# robot_board.net
KiCad netlist of a schematic drawn in EAGLE
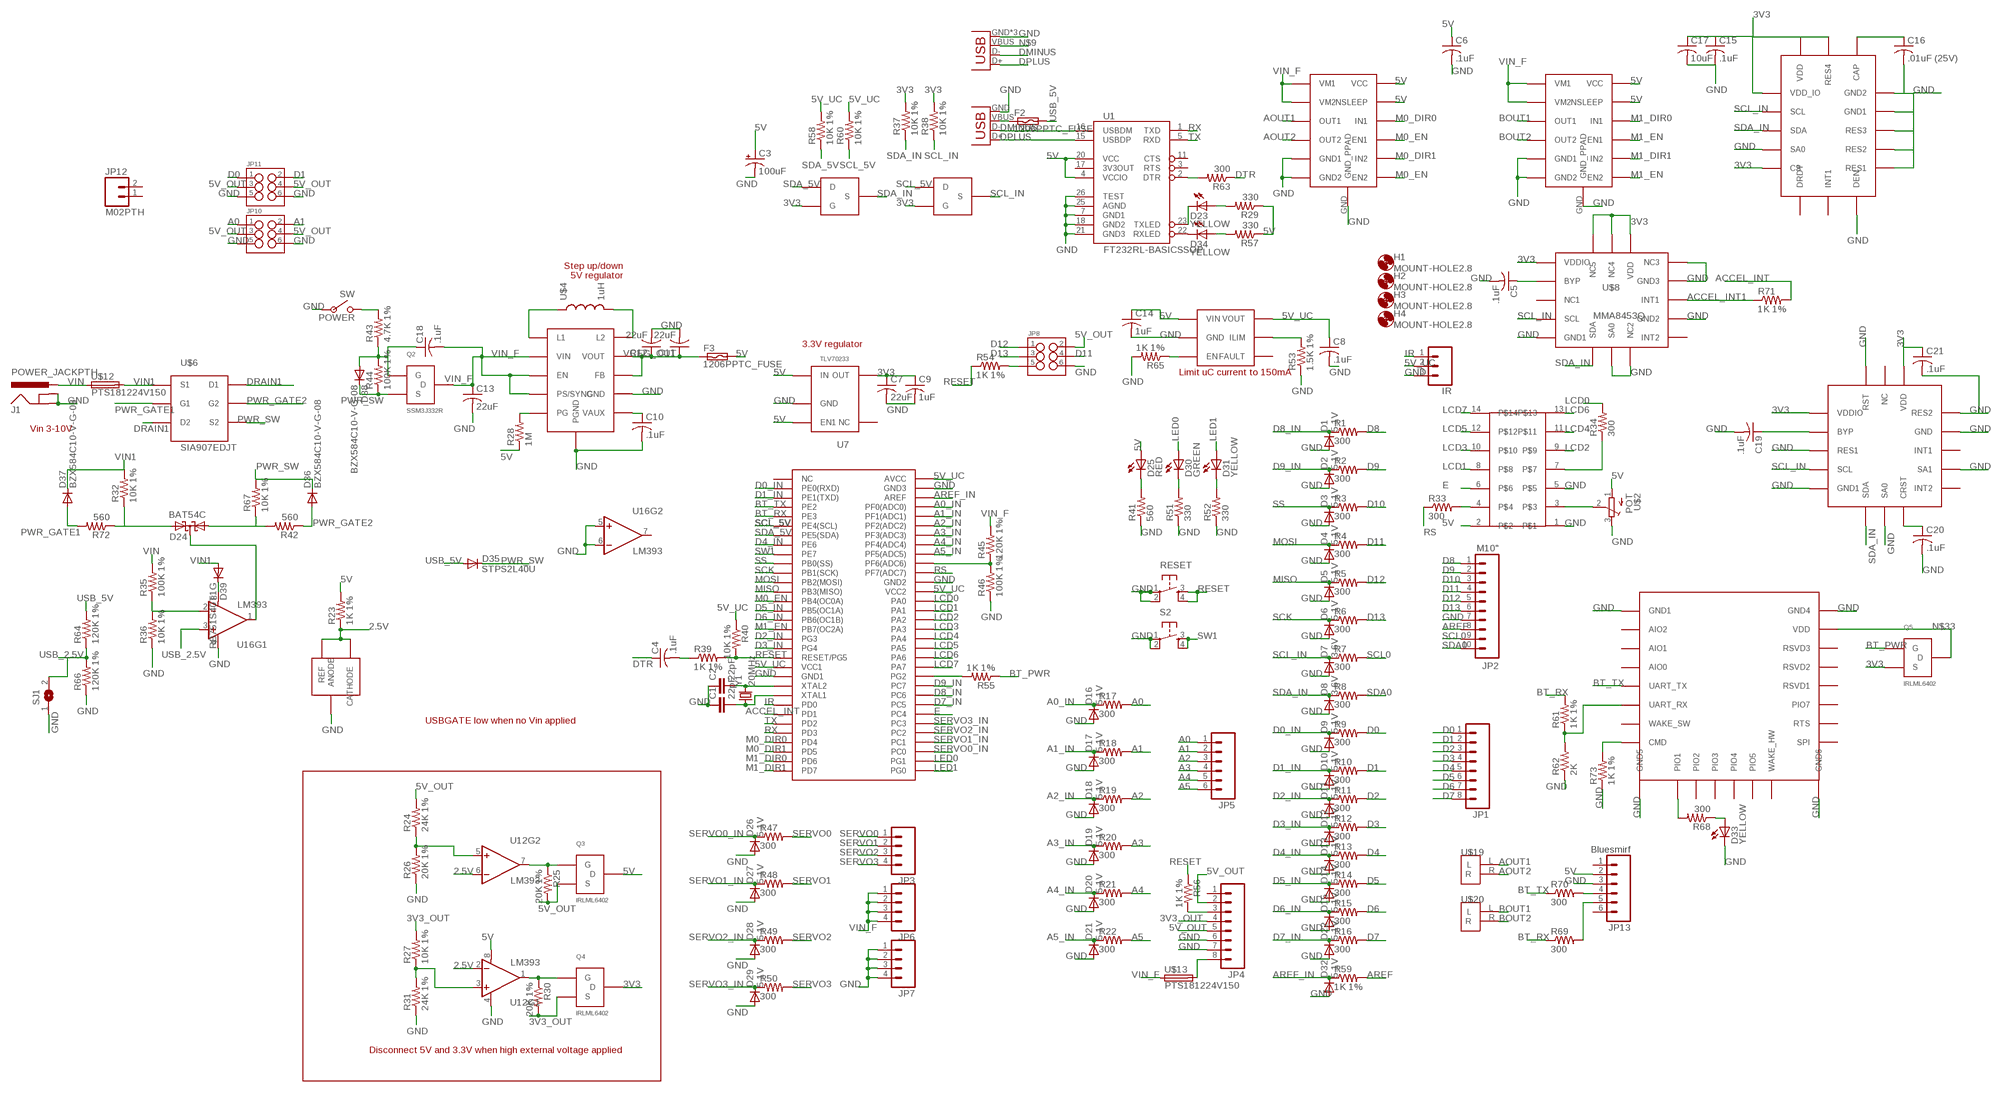
[diagram p0: schematic, sheet 1]

(export (version "E")
  (design (tool "Eeschema 10.0.6"))
  (components
    (comp (ref "C1")
      (value "22pF")
      (footprint "eagle-import:0805")
      (libsource (lib "eagle-import") (part "CAP0805"))
    )
    (comp (ref "C2")
      (value "22pF")
      (footprint "eagle-import:0805")
      (libsource (lib "eagle-import") (part "CAP0805"))
    )
    (comp (ref "C3")
      (value "100uF")
      (footprint "eagle-import:PANASONIC_D")
      (libsource (lib "eagle-import") (part "CAP_POLD"))
    )
    (comp (ref "C4")
      (value ".1uF")
      (footprint "eagle-import:C1206")
      (libsource (lib "eagle-import") (part "C-USC1206"))
    )
    (comp (ref "C5")
      (value ".1uF")
      (footprint "eagle-import:C1206")
      (libsource (lib "eagle-import") (part "C-USC1206"))
    )
    (comp (ref "C6")
      (value ".1uF")
      (footprint "eagle-import:C1206")
      (libsource (lib "eagle-import") (part "C-USC1206"))
    )
    (comp (ref "C7")
      (value "22uF")
      (footprint "eagle-import:C1206")
      (libsource (lib "eagle-import") (part "C-USC1206"))
    )
    (comp (ref "C8")
      (value ".1uF")
      (footprint "eagle-import:C1206")
      (libsource (lib "eagle-import") (part "C-USC1206"))
    )
    (comp (ref "C9")
      (value "1uF")
      (footprint "eagle-import:C1206")
      (libsource (lib "eagle-import") (part "C-USC1206"))
    )
    (comp (ref "C10")
      (value ".1uF")
      (footprint "eagle-import:C1206")
      (libsource (lib "eagle-import") (part "C-USC1206"))
    )
    (comp (ref "C11")
      (value "22uF")
      (footprint "eagle-import:C1206")
      (libsource (lib "eagle-import") (part "C-USC1206"))
    )
    (comp (ref "C12")
      (value "22uF")
      (footprint "eagle-import:C1206")
      (libsource (lib "eagle-import") (part "C-USC1206"))
    )
    (comp (ref "C13")
      (value "22uF")
      (footprint "eagle-import:C1206")
      (libsource (lib "eagle-import") (part "C-USC1206"))
    )
    (comp (ref "C14")
      (value "1uF")
      (footprint "eagle-import:C1206")
      (libsource (lib "eagle-import") (part "C-USC1206"))
    )
    (comp (ref "C15")
      (value ".1uF")
      (footprint "eagle-import:C1206")
      (libsource (lib "eagle-import") (part "C-USC1206"))
    )
    (comp (ref "C16")
      (value ".01uF (25V)")
      (footprint "eagle-import:C1206")
      (libsource (lib "eagle-import") (part "C-USC1206"))
    )
    (comp (ref "C17")
      (value "10uF")
      (footprint "eagle-import:C1206")
      (libsource (lib "eagle-import") (part "C-USC1206"))
    )
    (comp (ref "C18")
      (value ".1uF")
      (footprint "eagle-import:C1206")
      (libsource (lib "eagle-import") (part "C-USC1206"))
    )
    (comp (ref "C19")
      (value ".1uF")
      (footprint "eagle-import:C1206")
      (libsource (lib "eagle-import") (part "C-USC1206"))
    )
    (comp (ref "C20")
      (value ".1uF")
      (footprint "eagle-import:C1206")
      (libsource (lib "eagle-import") (part "C-USC1206"))
    )
    (comp (ref "C21")
      (value ".1uF")
      (footprint "eagle-import:C1206")
      (libsource (lib "eagle-import") (part "C-USC1206"))
    )
    (comp (ref "D1")
      (value "5.1V")
      (footprint "eagle-import:SOT23-3")
      (libsource (lib "eagle-import") (part "DIODESOT23"))
    )
    (comp (ref "D2")
      (value "5.1V")
      (footprint "eagle-import:SOT23-3")
      (libsource (lib "eagle-import") (part "DIODESOT23"))
    )
    (comp (ref "D3")
      (value "5.1V")
      (footprint "eagle-import:SOT23-3")
      (libsource (lib "eagle-import") (part "DIODESOT23"))
    )
    (comp (ref "D4")
      (value "5.1V")
      (footprint "eagle-import:SOT23-3")
      (libsource (lib "eagle-import") (part "DIODESOT23"))
    )
    (comp (ref "D5")
      (value "5.1V")
      (footprint "eagle-import:SOT23-3")
      (libsource (lib "eagle-import") (part "DIODESOT23"))
    )
    (comp (ref "D6")
      (value "5.1V")
      (footprint "eagle-import:SOT23-3")
      (libsource (lib "eagle-import") (part "DIODESOT23"))
    )
    (comp (ref "D7")
      (value "3.6V")
      (footprint "eagle-import:SOT23-3")
      (libsource (lib "eagle-import") (part "DIODESOT23"))
    )
    (comp (ref "D8")
      (value "3.6V")
      (footprint "eagle-import:SOT23-3")
      (libsource (lib "eagle-import") (part "DIODESOT23"))
    )
    (comp (ref "D9")
      (value "5.1V")
      (footprint "eagle-import:SOT23-3")
      (libsource (lib "eagle-import") (part "DIODESOT23"))
    )
    (comp (ref "D10")
      (value "5.1V")
      (footprint "eagle-import:SOT23-3")
      (libsource (lib "eagle-import") (part "DIODESOT23"))
    )
    (comp (ref "D11")
      (value "5.1V")
      (footprint "eagle-import:SOT23-3")
      (libsource (lib "eagle-import") (part "DIODESOT23"))
    )
    (comp (ref "D12")
      (value "5.1V")
      (footprint "eagle-import:SOT23-3")
      (libsource (lib "eagle-import") (part "DIODESOT23"))
    )
    (comp (ref "D13")
      (value "5.1V")
      (footprint "eagle-import:SOT23-3")
      (libsource (lib "eagle-import") (part "DIODESOT23"))
    )
    (comp (ref "D14")
      (value "5.1V")
      (footprint "eagle-import:SOT23-3")
      (libsource (lib "eagle-import") (part "DIODESOT23"))
    )
    (comp (ref "D15")
      (value "5.1V")
      (footprint "eagle-import:SOT23-3")
      (libsource (lib "eagle-import") (part "DIODESOT23"))
    )
    (comp (ref "D16")
      (value "5.1V")
      (footprint "eagle-import:SOT23-3")
      (libsource (lib "eagle-import") (part "DIODESOT23"))
    )
    (comp (ref "D17")
      (value "5.1V")
      (footprint "eagle-import:SOT23-3")
      (libsource (lib "eagle-import") (part "DIODESOT23"))
    )
    (comp (ref "D18")
      (value "5.1V")
      (footprint "eagle-import:SOT23-3")
      (libsource (lib "eagle-import") (part "DIODESOT23"))
    )
    (comp (ref "D19")
      (value "5.1V")
      (footprint "eagle-import:SOT23-3")
      (libsource (lib "eagle-import") (part "DIODESOT23"))
    )
    (comp (ref "D20")
      (value "5.1V")
      (footprint "eagle-import:SOT23-3")
      (libsource (lib "eagle-import") (part "DIODESOT23"))
    )
    (comp (ref "D21")
      (value "5.1V")
      (footprint "eagle-import:SOT23-3")
      (libsource (lib "eagle-import") (part "DIODESOT23"))
    )
    (comp (ref "D22")
      (value "5.1V")
      (footprint "eagle-import:SOT23-3")
      (libsource (lib "eagle-import") (part "DIODESOT23"))
    )
    (comp (ref "D23")
      (value "YELLOW")
      (footprint "eagle-import:LED-1206")
      (libsource (lib "eagle-import") (part "LED-GREENLILYPAD"))
    )
    (comp (ref "D24")
      (value "BAT54C")
      (footprint "eagle-import:SOT23")
      (libsource (lib "eagle-import") (part "BAT54C"))
    )
    (comp (ref "D25")
      (value "RED")
      (footprint "eagle-import:LED-1206")
      (libsource (lib "eagle-import") (part "LED-GREENLILYPAD"))
    )
    (comp (ref "D26")
      (value "5.1V")
      (footprint "eagle-import:SOT23-3")
      (libsource (lib "eagle-import") (part "DIODESOT23"))
    )
    (comp (ref "D27")
      (value "5.1V")
      (footprint "eagle-import:SOT23-3")
      (libsource (lib "eagle-import") (part "DIODESOT23"))
    )
    (comp (ref "D28")
      (value "5.1V")
      (footprint "eagle-import:SOT23-3")
      (libsource (lib "eagle-import") (part "DIODESOT23"))
    )
    (comp (ref "D29")
      (value "5.1V")
      (footprint "eagle-import:SOT23-3")
      (libsource (lib "eagle-import") (part "DIODESOT23"))
    )
    (comp (ref "D30")
      (value "GREEN")
      (footprint "eagle-import:LED-1206")
      (libsource (lib "eagle-import") (part "LED-GREENLILYPAD"))
    )
    (comp (ref "D31")
      (value "YELLOW")
      (footprint "eagle-import:LED-1206")
      (libsource (lib "eagle-import") (part "LED-GREENLILYPAD"))
    )
    (comp (ref "D32")
      (value "5.1V")
      (footprint "eagle-import:SOT23-3")
      (libsource (lib "eagle-import") (part "DIODESOT23"))
    )
    (comp (ref "D33")
      (value "YELLOW")
      (footprint "eagle-import:LED-1206")
      (libsource (lib "eagle-import") (part "LED-GREENLILYPAD"))
    )
    (comp (ref "D34")
      (value "YELLOW")
      (footprint "eagle-import:LED-1206")
      (libsource (lib "eagle-import") (part "LED-GREENLILYPAD"))
    )
    (comp (ref "D35")
      (value "STPS2L40U")
      (footprint "eagle-import:SMA-DIODE")
      (libsource (lib "eagle-import") (part "DIODESMA"))
    )
    (comp (ref "D36")
      (value "BZX584C10-V-G-08")
      (footprint "eagle-import:SOD523")
      (libsource (lib "eagle-import") (part "DIODESOD523"))
    )
    (comp (ref "D37")
      (value "BZX584C10-V-G-08")
      (footprint "eagle-import:SOD523")
      (libsource (lib "eagle-import") (part "DIODESOD523"))
    )
    (comp (ref "D38")
      (value "BZX584C10-V-G-08")
      (footprint "eagle-import:SOD523")
      (libsource (lib "eagle-import") (part "DIODESOD523"))
    )
    (comp (ref "D39")
      (value "RB751S40T1G")
      (footprint "eagle-import:SOD523")
      (libsource (lib "eagle-import") (part "DIODESOD523"))
    )
    (comp (ref "F2")
      (value "1206PPTC_FUSE")
      (footprint "eagle-import:R1206")
      (libsource (lib "eagle-import") (part "1206PPTC_FUSE"))
    )
    (comp (ref "F3")
      (value "1206PPTC_FUSE")
      (footprint "eagle-import:R1206")
      (libsource (lib "eagle-import") (part "1206PPTC_FUSE"))
    )
    (comp (ref "H1")
      (value "MOUNT-HOLE2.8")
      (footprint "eagle-import:2,8")
      (libsource (lib "eagle-import") (part "MOUNT-HOLE2.8"))
    )
    (comp (ref "H2")
      (value "MOUNT-HOLE2.8")
      (footprint "eagle-import:2,8")
      (libsource (lib "eagle-import") (part "MOUNT-HOLE2.8"))
    )
    (comp (ref "H3")
      (value "MOUNT-HOLE2.8")
      (footprint "eagle-import:2,8")
      (libsource (lib "eagle-import") (part "MOUNT-HOLE2.8"))
    )
    (comp (ref "H4")
      (value "MOUNT-HOLE2.8")
      (footprint "eagle-import:2,8")
      (libsource (lib "eagle-import") (part "MOUNT-HOLE2.8"))
    )
    (comp (ref "IR")
      (value "M03PTH")
      (footprint "eagle-import:1X03")
      (libsource (lib "eagle-import") (part "M03PTH"))
    )
    (comp (ref "J1")
      (value "POWER_JACKPTH")
      (footprint "eagle-import:POWER_JACK_PTH")
      (libsource (lib "eagle-import") (part "POWER_JACKPTH"))
    )
    (comp (ref "JP1")
      (value "M081X08")
      (footprint "eagle-import:1X08")
      (libsource (lib "eagle-import") (part "M081X08"))
    )
    (comp (ref "JP2")
      (value "M10\"")
      (footprint "eagle-import:1X10")
      (libsource (lib "eagle-import") (part "M10{dblquote}"))
    )
    (comp (ref "JP3")
      (value "M04PTH")
      (footprint "eagle-import:1X04")
      (libsource (lib "eagle-import") (part "M04PTH"))
    )
    (comp (ref "JP4")
      (value "M081X08")
      (footprint "eagle-import:1X08")
      (libsource (lib "eagle-import") (part "M081X08"))
    )
    (comp (ref "JP5")
      (value "M06SIP")
      (footprint "eagle-import:1X06")
      (libsource (lib "eagle-import") (part "M06SIP"))
    )
    (comp (ref "JP6")
      (value "M04PTH")
      (footprint "eagle-import:1X04")
      (libsource (lib "eagle-import") (part "M04PTH"))
    )
    (comp (ref "JP7")
      (value "M04PTH")
      (footprint "eagle-import:1X04")
      (libsource (lib "eagle-import") (part "M04PTH"))
    )
    (comp (ref "JP8")
      (value "M03X22X3_SILK_SM")
      (footprint "eagle-import:2X3")
      (libsource (lib "eagle-import") (part "M03X22X3_SILK_SM"))
    )
    (comp (ref "JP9")
      (value "USB-B")
      (footprint "eagle-import:USB-B-PTH")
      (libsource (lib "eagle-import") (part "USBPTH"))
    )
    (comp (ref "JP10")
      (value "M03X22X3_SILK_SM")
      (footprint "eagle-import:2X3")
      (libsource (lib "eagle-import") (part "M03X22X3_SILK_SM"))
    )
    (comp (ref "JP11")
      (value "M03X22X3_SILK_SM")
      (footprint "eagle-import:2X3")
      (libsource (lib "eagle-import") (part "M03X22X3_SILK_SM"))
    )
    (comp (ref "JP12")
      (value "M02PTH")
      (footprint "eagle-import:1X02")
      (libsource (lib "eagle-import") (part "M02PTH"))
    )
    (comp (ref "JP13")
      (value "Bluesmirf")
      (footprint "eagle-import:1X06")
      (libsource (lib "eagle-import") (part "M06SIP"))
    )
    (comp (ref "JP14")
      (value "USB-MICROB")
      (footprint "eagle-import:USB-MICROB")
      (libsource (lib "eagle-import") (part "USB-MICROB"))
    )
    (comp (ref "POWER")
      (value "SW")
      (footprint "eagle-import:SW")
      (libsource (lib "eagle-import") (part "SW"))
    )
    (comp (ref "Q2")
      (value "SSM3J332R")
      (footprint "eagle-import:SOT23")
      (libsource (lib "eagle-import") (part "DMP2035U"))
    )
    (comp (ref "Q3")
      (value "IRLML6402")
      (footprint "eagle-import:SOT23")
      (libsource (lib "eagle-import") (part "DMP2035U"))
    )
    (comp (ref "Q4")
      (value "IRLML6402")
      (footprint "eagle-import:SOT23")
      (libsource (lib "eagle-import") (part "DMP2035U"))
    )
    (comp (ref "Q5")
      (value "IRLML6402")
      (footprint "eagle-import:SOT23")
      (libsource (lib "eagle-import") (part "DMP2035U"))
    )
    (comp (ref "R1")
      (value "300")
      (footprint "eagle-import:R1206")
      (libsource (lib "eagle-import") (part "R-US_R1206"))
    )
    (comp (ref "R2")
      (value "300")
      (footprint "eagle-import:R1206")
      (libsource (lib "eagle-import") (part "R-US_R1206"))
    )
    (comp (ref "R3")
      (value "300")
      (footprint "eagle-import:R1206")
      (libsource (lib "eagle-import") (part "R-US_R1206"))
    )
    (comp (ref "R4")
      (value "300")
      (footprint "eagle-import:R1206")
      (libsource (lib "eagle-import") (part "R-US_R1206"))
    )
    (comp (ref "R5")
      (value "300")
      (footprint "eagle-import:R1206")
      (libsource (lib "eagle-import") (part "R-US_R1206"))
    )
    (comp (ref "R6")
      (value "300")
      (footprint "eagle-import:R1206")
      (libsource (lib "eagle-import") (part "R-US_R1206"))
    )
    (comp (ref "R7")
      (value "300")
      (footprint "eagle-import:R1206")
      (libsource (lib "eagle-import") (part "R-US_R1206"))
    )
    (comp (ref "R8")
      (value "300")
      (footprint "eagle-import:R1206")
      (libsource (lib "eagle-import") (part "R-US_R1206"))
    )
    (comp (ref "R9")
      (value "300")
      (footprint "eagle-import:R1206")
      (libsource (lib "eagle-import") (part "R-US_R1206"))
    )
    (comp (ref "R10")
      (value "300")
      (footprint "eagle-import:R1206")
      (libsource (lib "eagle-import") (part "R-US_R1206"))
    )
    (comp (ref "R11")
      (value "300")
      (footprint "eagle-import:R1206")
      (libsource (lib "eagle-import") (part "R-US_R1206"))
    )
    (comp (ref "R12")
      (value "300")
      (footprint "eagle-import:R1206")
      (libsource (lib "eagle-import") (part "R-US_R1206"))
    )
    (comp (ref "R13")
      (value "300")
      (footprint "eagle-import:R1206")
      (libsource (lib "eagle-import") (part "R-US_R1206"))
    )
    (comp (ref "R14")
      (value "300")
      (footprint "eagle-import:R1206")
      (libsource (lib "eagle-import") (part "R-US_R1206"))
    )
    (comp (ref "R15")
      (value "300")
      (footprint "eagle-import:R1206")
      (libsource (lib "eagle-import") (part "R-US_R1206"))
    )
    (comp (ref "R16")
      (value "300")
      (footprint "eagle-import:R1206")
      (libsource (lib "eagle-import") (part "R-US_R1206"))
    )
    (comp (ref "R17")
      (value "300")
      (footprint "eagle-import:R1206")
      (libsource (lib "eagle-import") (part "R-US_R1206"))
    )
    (comp (ref "R18")
      (value "300")
      (footprint "eagle-import:R1206")
      (libsource (lib "eagle-import") (part "R-US_R1206"))
    )
    (comp (ref "R19")
      (value "300")
      (footprint "eagle-import:R1206")
      (libsource (lib "eagle-import") (part "R-US_R1206"))
    )
    (comp (ref "R20")
      (value "300")
      (footprint "eagle-import:R1206")
      (libsource (lib "eagle-import") (part "R-US_R1206"))
    )
    (comp (ref "R21")
      (value "300")
      (footprint "eagle-import:R1206")
      (libsource (lib "eagle-import") (part "R-US_R1206"))
    )
    (comp (ref "R22")
      (value "300")
      (footprint "eagle-import:R1206")
      (libsource (lib "eagle-import") (part "R-US_R1206"))
    )
    (comp (ref "R23")
      (value "1K 1%")
      (footprint "eagle-import:R1206")
      (libsource (lib "eagle-import") (part "R-US_R1206"))
    )
    (comp (ref "R24")
      (value "24K 1%")
      (footprint "eagle-import:R1206")
      (libsource (lib "eagle-import") (part "R-US_R1206"))
    )
    (comp (ref "R25")
      (value "20K 1%")
      (footprint "eagle-import:R1206")
      (libsource (lib "eagle-import") (part "R-US_R1206"))
    )
    (comp (ref "R26")
      (value "20K 1%")
      (footprint "eagle-import:R1206")
      (libsource (lib "eagle-import") (part "R-US_R1206"))
    )
    (comp (ref "R27")
      (value "10K 1%")
      (footprint "eagle-import:R1206")
      (libsource (lib "eagle-import") (part "R-US_R1206"))
    )
    (comp (ref "R28")
      (value "1M")
      (footprint "eagle-import:R1206")
      (libsource (lib "eagle-import") (part "R-US_R1206"))
    )
    (comp (ref "R29")
      (value "330")
      (footprint "eagle-import:R1206")
      (libsource (lib "eagle-import") (part "R-US_R1206"))
    )
    (comp (ref "R30")
      (value "20K 1%")
      (footprint "eagle-import:R1206")
      (libsource (lib "eagle-import") (part "R-US_R1206"))
    )
    (comp (ref "R31")
      (value "24K 1%")
      (footprint "eagle-import:R1206")
      (libsource (lib "eagle-import") (part "R-US_R1206"))
    )
    (comp (ref "R32")
      (value "10K 1%")
      (footprint "eagle-import:R1206")
      (libsource (lib "eagle-import") (part "R-US_R1206"))
    )
    (comp (ref "R33")
      (value "300")
      (footprint "eagle-import:R1206")
      (libsource (lib "eagle-import") (part "R-US_R1206"))
    )
    (comp (ref "R34")
      (value "300")
      (footprint "eagle-import:R1206")
      (libsource (lib "eagle-import") (part "R-US_R1206"))
    )
    (comp (ref "R35")
      (value "100K 1%")
      (footprint "eagle-import:R1206")
      (libsource (lib "eagle-import") (part "R-US_R1206"))
    )
    (comp (ref "R36")
      (value "10K 1%")
      (footprint "eagle-import:R1206")
      (libsource (lib "eagle-import") (part "R-US_R1206"))
    )
    (comp (ref "R37")
      (value "10K 1%")
      (footprint "eagle-import:R1206")
      (libsource (lib "eagle-import") (part "R-US_R1206"))
    )
    (comp (ref "R38")
      (value "10K 1%")
      (footprint "eagle-import:R1206")
      (libsource (lib "eagle-import") (part "R-US_R1206"))
    )
    (comp (ref "R39")
      (value "1K 1%")
      (footprint "eagle-import:R1206")
      (libsource (lib "eagle-import") (part "R-US_R1206"))
    )
    (comp (ref "R40")
      (value "10K 1%")
      (footprint "eagle-import:R1206")
      (libsource (lib "eagle-import") (part "R-US_R1206"))
    )
    (comp (ref "R41")
      (value "560")
      (footprint "eagle-import:R1206")
      (libsource (lib "eagle-import") (part "R-US_R1206"))
    )
    (comp (ref "R42")
      (value "560")
      (footprint "eagle-import:R1206")
      (libsource (lib "eagle-import") (part "R-US_R1206"))
    )
    (comp (ref "R43")
      (value "4.7K 1%")
      (footprint "eagle-import:R1206")
      (libsource (lib "eagle-import") (part "R-US_R1206"))
    )
    (comp (ref "R44")
      (value "100K 1%")
      (footprint "eagle-import:R1206")
      (libsource (lib "eagle-import") (part "R-US_R1206"))
    )
    (comp (ref "R45")
      (value "120K 1%")
      (footprint "eagle-import:R1206")
      (libsource (lib "eagle-import") (part "R-US_R1206"))
    )
    (comp (ref "R46")
      (value "100K 1%")
      (footprint "eagle-import:R1206")
      (libsource (lib "eagle-import") (part "R-US_R1206"))
    )
    (comp (ref "R47")
      (value "300")
      (footprint "eagle-import:R1206")
      (libsource (lib "eagle-import") (part "R-US_R1206"))
    )
    (comp (ref "R48")
      (value "300")
      (footprint "eagle-import:R1206")
      (libsource (lib "eagle-import") (part "R-US_R1206"))
    )
    (comp (ref "R49")
      (value "300")
      (footprint "eagle-import:R1206")
      (libsource (lib "eagle-import") (part "R-US_R1206"))
    )
    (comp (ref "R50")
      (value "300")
      (footprint "eagle-import:R1206")
      (libsource (lib "eagle-import") (part "R-US_R1206"))
    )
    (comp (ref "R51")
      (value "330")
      (footprint "eagle-import:R1206")
      (libsource (lib "eagle-import") (part "R-US_R1206"))
    )
    (comp (ref "R52")
      (value "330")
      (footprint "eagle-import:R1206")
      (libsource (lib "eagle-import") (part "R-US_R1206"))
    )
    (comp (ref "R53")
      (value "1.5K 1%")
      (footprint "eagle-import:R1206")
      (libsource (lib "eagle-import") (part "R-US_R1206"))
    )
    (comp (ref "R54")
      (value "1K 1%")
      (footprint "eagle-import:R1206")
      (libsource (lib "eagle-import") (part "R-US_R1206"))
    )
    (comp (ref "R55")
      (value "1K 1%")
      (footprint "eagle-import:R1206")
      (libsource (lib "eagle-import") (part "R-US_R1206"))
    )
    (comp (ref "R56")
      (value "1K 1%")
      (footprint "eagle-import:R1206")
      (libsource (lib "eagle-import") (part "R-US_R1206"))
    )
    (comp (ref "R57")
      (value "330")
      (footprint "eagle-import:R1206")
      (libsource (lib "eagle-import") (part "R-US_R1206"))
    )
    (comp (ref "R58")
      (value "10K 1%")
      (footprint "eagle-import:R1206")
      (libsource (lib "eagle-import") (part "R-US_R1206"))
    )
    (comp (ref "R59")
      (value "1K 1%")
      (footprint "eagle-import:R1206")
      (libsource (lib "eagle-import") (part "R-US_R1206"))
    )
    (comp (ref "R60")
      (value "10K 1%")
      (footprint "eagle-import:R1206")
      (libsource (lib "eagle-import") (part "R-US_R1206"))
    )
    (comp (ref "R61")
      (value "1K 1%")
      (footprint "eagle-import:R1206")
      (libsource (lib "eagle-import") (part "R-US_R1206"))
    )
    (comp (ref "R62")
      (value "2K")
      (footprint "eagle-import:R1206")
      (libsource (lib "eagle-import") (part "R-US_R1206"))
    )
    (comp (ref "R63")
      (value "300")
      (footprint "eagle-import:R1206")
      (libsource (lib "eagle-import") (part "R-US_R1206"))
    )
    (comp (ref "R64")
      (value "120K 1%")
      (footprint "eagle-import:R1206")
      (libsource (lib "eagle-import") (part "R-US_R1206"))
    )
    (comp (ref "R65")
      (value "1K 1%")
      (footprint "eagle-import:R1206")
      (libsource (lib "eagle-import") (part "R-US_R1206"))
    )
    (comp (ref "R66")
      (value "120K 1%")
      (footprint "eagle-import:R1206")
      (libsource (lib "eagle-import") (part "R-US_R1206"))
    )
    (comp (ref "R67")
      (value "10K 1%")
      (footprint "eagle-import:R1206")
      (libsource (lib "eagle-import") (part "R-US_R1206"))
    )
    (comp (ref "R68")
      (value "300")
      (footprint "eagle-import:R1206")
      (libsource (lib "eagle-import") (part "R-US_R1206"))
    )
    (comp (ref "R69")
      (value "300")
      (footprint "eagle-import:R1206")
      (libsource (lib "eagle-import") (part "R-US_R1206"))
    )
    (comp (ref "R70")
      (value "300")
      (footprint "eagle-import:R1206")
      (libsource (lib "eagle-import") (part "R-US_R1206"))
    )
    (comp (ref "R71")
      (value "1K 1%")
      (footprint "eagle-import:R1206")
      (libsource (lib "eagle-import") (part "R-US_R1206"))
    )
    (comp (ref "R72")
      (value "560")
      (footprint "eagle-import:R1206")
      (libsource (lib "eagle-import") (part "R-US_R1206"))
    )
    (comp (ref "R73")
      (value "1K 1%")
      (footprint "eagle-import:R1206")
      (libsource (lib "eagle-import") (part "R-US_R1206"))
    )
    (comp (ref "RESET")
      (value "TAC_SWITCHPTH")
      (footprint "eagle-import:TACTILE-PTH")
      (libsource (lib "eagle-import") (part "TAC_SWITCHPTH"))
    )
    (comp (ref "S2")
      (value "TAC_SWITCHPTH")
      (footprint "eagle-import:TACTILE-PTH")
      (libsource (lib "eagle-import") (part "TAC_SWITCHPTH"))
    )
    (comp (ref "SJ1")
      (value "SJW")
      (footprint "eagle-import:SJW")
      (libsource (lib "eagle-import") (part "SJW"))
    )
    (comp (ref "U$1")
      (value "2X7HEADER")
      (footprint "eagle-import:2X7")
      (libsource (lib "eagle-import") (part "2X7HEADER"))
    )
    (comp (ref "U$2")
      (value "POT")
      (footprint "eagle-import:POT")
      (libsource (lib "eagle-import") (part "POT"))
    )
    (comp (ref "U$3")
      (value "TPS63061")
      (footprint "eagle-import:WSON-10")
      (libsource (lib "eagle-import") (part "TPS63061"))
    )
    (comp (ref "U$4")
      (value "1uH")
      (footprint "eagle-import:TAIYO4012")
      (libsource (lib "eagle-import") (part "TAIYO4012"))
    )
    (comp (ref "U$5")
      (value "AP431SAG-7")
      (footprint "eagle-import:SOT23")
      (libsource (lib "eagle-import") (part "AP431SAG-7"))
    )
    (comp (ref "U$6")
      (value "SIA907EDJT")
      (footprint "eagle-import:SC70T")
      (libsource (lib "eagle-import") (part "SIA907EDJT"))
    )
    (comp (ref "U$7")
      (value "RN4020")
      (footprint "eagle-import:RN4020_PKG")
      (libsource (lib "eagle-import") (part "RN4020"))
    )
    (comp (ref "U$8")
      (value "MMA8453Q")
      (footprint "eagle-import:QFN-COL")
      (libsource (lib "eagle-import") (part "MMA8453Q"))
    )
    (comp (ref "U$9")
      (value "BSS138")
      (footprint "eagle-import:SOT23")
      (libsource (lib "eagle-import") (part "BSS138"))
    )
    (comp (ref "U$10")
      (value "BSS138")
      (footprint "eagle-import:SOT23")
      (libsource (lib "eagle-import") (part "BSS138"))
    )
    (comp (ref "U$11")
      (value "L3GD20HTR")
      (footprint "eagle-import:LGA-16")
      (libsource (lib "eagle-import") (part "L3GD20HTR"))
    )
    (comp (ref "U$12")
      (value "PTS181224V150")
      (footprint "eagle-import:C1812")
      (libsource (lib "eagle-import") (part "PTS181224V150"))
    )
    (comp (ref "U$13")
      (value "PTS181224V150")
      (footprint "eagle-import:C1812")
      (libsource (lib "eagle-import") (part "PTS181224V150"))
    )
    (comp (ref "U$14")
      (value "FXOS8700CQ")
      (footprint "eagle-import:FSOS8700CQ_PKG")
      (libsource (lib "eagle-import") (part "FXOS8700CQ"))
    )
    (comp (ref "U$19")
      (value "2POS_TERMINAL")
      (footprint "eagle-import:2POS_TERMINAL")
      (libsource (lib "eagle-import") (part "2POS_TERMINAL"))
    )
    (comp (ref "U$20")
      (value "2POS_TERMINAL")
      (footprint "eagle-import:2POS_TERMINAL")
      (libsource (lib "eagle-import") (part "2POS_TERMINAL"))
    )
    (comp (ref "U1")
      (value "FT232RL-BASICSSOP")
      (footprint "eagle-import:SSOP28DB")
      (libsource (lib "eagle-import") (part "FT232RL-BASICSSOP"))
    )
    (comp (ref "U7")
      (value "TLV70233")
      (footprint "eagle-import:SOT-23-5")
      (libsource (lib "eagle-import") (part "TLV70233"))
    )
    (comp (ref "U8")
      (value "MIC2009A")
      (footprint "eagle-import:SOT23-M5")
      (libsource (lib "eagle-import") (part "MIC2009A"))
    )
    (comp (ref "U9")
      (value "DRV8839")
      (footprint "eagle-import:PWSON-N12")
      (libsource (lib "eagle-import") (part "DRV8839"))
    )
    (comp (ref "U10")
      (value "DRV8839")
      (footprint "eagle-import:PWSON-N12")
      (libsource (lib "eagle-import") (part "DRV8839"))
    )
    (comp (ref "U12")
      (value "LM393")
      (footprint "eagle-import:SO08")
      (libsource (lib "eagle-import") (part "LM393"))
    )
    (comp (ref "U16")
      (value "LM393")
      (footprint "eagle-import:SO08")
      (libsource (lib "eagle-import") (part "LM393"))
    )
    (comp (ref "U17")
      (value "ATMEGA325PA")
      (footprint "eagle-import:TQFP64")
      (libsource (lib "eagle-import") (part "ATMEGA325PA"))
    )
    (comp (ref "Y1")
      (value "20MHz")
      (footprint "eagle-import:CRYSTAL-SMD-10.5X4.8-2PIN")
      (libsource (lib "eagle-import") (part "CRYSTAL10.5X4.8"))
    )
  )
  (nets
    (net (code "1") (name "/2.5V") (class "Default")
      (node (ref "R23") (pin "1") (pinfunction "1_1") (pintype "passive"))
      (node (ref "U$5") (pin "1") (pinfunction "CATHODE_1") (pintype "bidirectional"))
      (node (ref "U$5") (pin "2") (pinfunction "REF_2") (pintype "bidirectional"))
      (node (ref "U12") (pin "2") (pinfunction "-IN_2") (pintype "input"))
      (node (ref "U12") (pin "6") (pinfunction "-IN_6") (pintype "input"))
    )
    (net (code "2") (name "/3V3") (class "Default")
      (node (ref "C15") (pin "1") (pinfunction "1_1") (pintype "passive"))
      (node (ref "C17") (pin "1") (pinfunction "1_1") (pintype "passive"))
      (node (ref "C21") (pin "1") (pinfunction "1_1") (pintype "passive"))
      (node (ref "C7") (pin "1") (pinfunction "1_1") (pintype "passive"))
      (node (ref "C9") (pin "1") (pinfunction "1_1") (pintype "passive"))
      (node (ref "Q4") (pin "3") (pinfunction "D_3") (pintype "bidirectional"))
      (node (ref "Q5") (pin "2") (pinfunction "S_2") (pintype "bidirectional"))
      (node (ref "R37") (pin "2") (pinfunction "2_2") (pintype "passive"))
      (node (ref "R38") (pin "2") (pinfunction "2_2") (pintype "passive"))
      (node (ref "U$10") (pin "1") (pinfunction "G_1") (pintype "bidirectional"))
      (node (ref "U$11") (pin "P$1") (pinfunction "VDD_IO_P$1") (pintype "bidirectional"))
      (node (ref "U$11") (pin "P$15") (pinfunction "RES4_P$15") (pintype "bidirectional"))
      (node (ref "U$11") (pin "P$16") (pinfunction "VDD_P$16") (pintype "bidirectional"))
      (node (ref "U$11") (pin "P$5") (pinfunction "CS_P$5") (pintype "bidirectional"))
      (node (ref "U$14") (pin "P$1") (pinfunction "VDDIO_P$1") (pintype "bidirectional"))
      (node (ref "U$14") (pin "P$14") (pinfunction "VDD_P$14") (pintype "bidirectional"))
      (node (ref "U$8") (pin "P$1") (pinfunction "VDDIO_P$1") (pintype "bidirectional"))
      (node (ref "U$8") (pin "P$14") (pinfunction "VDD_P$14") (pintype "bidirectional"))
      (node (ref "U$8") (pin "P$15") (pinfunction "NC4_P$15") (pintype "bidirectional"))
      (node (ref "U$8") (pin "P$16") (pinfunction "NC5_P$16") (pintype "bidirectional"))
      (node (ref "U$9") (pin "1") (pinfunction "G_1") (pintype "bidirectional"))
      (node (ref "U7") (pin "P$4") (pinfunction "OUT_P$4") (pintype "bidirectional"))
    )
    (net (code "3") (name "/3V3_OUT") (class "Default")
      (node (ref "JP4") (pin "4") (pinfunction "4_4") (pintype "passive"))
      (node (ref "Q4") (pin "2") (pinfunction "S_2") (pintype "bidirectional"))
      (node (ref "R27") (pin "2") (pinfunction "2_2") (pintype "passive"))
      (node (ref "R30") (pin "2") (pinfunction "2_2") (pintype "passive"))
    )
    (net (code "4") (name "/5V") (class "Default")
      (node (ref "C14") (pin "1") (pinfunction "1_1") (pintype "passive"))
      (node (ref "C3") (pin "+") (pinfunction "+_+") (pintype "passive"))
      (node (ref "C6") (pin "1") (pinfunction "1_1") (pintype "passive"))
      (node (ref "D25") (pin "A") (pinfunction "A_A") (pintype "passive"))
      (node (ref "F3") (pin "2") (pinfunction "2_2") (pintype "passive"))
      (node (ref "JP13") (pin "2") (pinfunction "2_2") (pintype "passive"))
      (node (ref "Q3") (pin "3") (pinfunction "D_3") (pintype "bidirectional"))
      (node (ref "R23") (pin "2") (pinfunction "2_2") (pintype "passive"))
      (node (ref "R28") (pin "1") (pinfunction "1_1") (pintype "passive"))
      (node (ref "R29") (pin "1") (pinfunction "1_1") (pintype "passive"))
      (node (ref "R57") (pin "1") (pinfunction "1_1") (pintype "passive"))
      (node (ref "U$1") (pin "2") (pinfunction "P$2_2") (pintype "bidirectional"))
      (node (ref "U$2") (pin "1") (pinfunction "A_1") (pintype "passive"))
      (node (ref "U1") (pin "20") (pinfunction "VCC_20") (pintype "power_in"))
      (node (ref "U1") (pin "4") (pinfunction "VCCIO_4") (pintype "power_in"))
      (node (ref "U10") (pin "P$7") (pinfunction "VCC_P$7") (pintype "bidirectional"))
      (node (ref "U10") (pin "P$8") (pinfunction "NSLEEP_P$8") (pintype "bidirectional"))
      (node (ref "U12") (pin "8") (pinfunction "V+_8") (pintype "power_in"))
      (node (ref "U7") (pin "P$1") (pinfunction "IN_P$1") (pintype "bidirectional"))
      (node (ref "U7") (pin "P$3") (pinfunction "EN1_P$3") (pintype "bidirectional"))
      (node (ref "U8") (pin "P$1") (pinfunction "VIN_P$1") (pintype "bidirectional"))
      (node (ref "U9") (pin "P$7") (pinfunction "VCC_P$7") (pintype "bidirectional"))
      (node (ref "U9") (pin "P$8") (pinfunction "NSLEEP_P$8") (pintype "bidirectional"))
    )
    (net (code "5") (name "/5V_OUT") (class "Default")
      (node (ref "JP10") (pin "3") (pinfunction "3_3") (pintype "bidirectional"))
      (node (ref "JP10") (pin "4") (pinfunction "4_4") (pintype "bidirectional"))
      (node (ref "JP11") (pin "3") (pinfunction "3_3") (pintype "bidirectional"))
      (node (ref "JP11") (pin "4") (pinfunction "4_4") (pintype "bidirectional"))
      (node (ref "JP4") (pin "2") (pinfunction "2_2") (pintype "passive"))
      (node (ref "JP4") (pin "5") (pinfunction "5_5") (pintype "passive"))
      (node (ref "JP8") (pin "2") (pinfunction "2_2") (pintype "bidirectional"))
      (node (ref "Q3") (pin "2") (pinfunction "S_2") (pintype "bidirectional"))
      (node (ref "R24") (pin "2") (pinfunction "2_2") (pintype "passive"))
      (node (ref "R25") (pin "2") (pinfunction "2_2") (pintype "passive"))
    )
    (net (code "6") (name "/5V_UC") (class "Default")
      (node (ref "C8") (pin "1") (pinfunction "1_1") (pintype "passive"))
      (node (ref "IR") (pin "2") (pinfunction "2_2") (pintype "passive"))
      (node (ref "R40") (pin "1") (pinfunction "1_1") (pintype "passive"))
      (node (ref "R58") (pin "2") (pinfunction "2_2") (pintype "passive"))
      (node (ref "R60") (pin "2") (pinfunction "2_2") (pintype "passive"))
      (node (ref "U17") (pin "21") (pinfunction "VCC1_21") (pintype "bidirectional"))
      (node (ref "U17") (pin "52") (pinfunction "VCC2_52") (pintype "bidirectional"))
      (node (ref "U17") (pin "64") (pinfunction "AVCC_64") (pintype "bidirectional"))
      (node (ref "U8") (pin "P$6") (pinfunction "VOUT_P$6") (pintype "bidirectional"))
    )
    (net (code "7") (name "/A0") (class "Default")
      (node (ref "JP10") (pin "1") (pinfunction "1_1") (pintype "bidirectional"))
      (node (ref "JP5") (pin "1") (pinfunction "1_1") (pintype "passive"))
      (node (ref "R17") (pin "2") (pinfunction "2_2") (pintype "passive"))
    )
    (net (code "8") (name "/A0_IN") (class "Default")
      (node (ref "D16") (pin "3") (pinfunction "C_3") (pintype "passive"))
      (node (ref "R17") (pin "1") (pinfunction "1_1") (pintype "passive"))
      (node (ref "U17") (pin "61") (pinfunction "PF0(ADC0)_61") (pintype "bidirectional"))
    )
    (net (code "9") (name "/A1") (class "Default")
      (node (ref "JP10") (pin "2") (pinfunction "2_2") (pintype "bidirectional"))
      (node (ref "JP5") (pin "2") (pinfunction "2_2") (pintype "passive"))
      (node (ref "R18") (pin "2") (pinfunction "2_2") (pintype "passive"))
    )
    (net (code "10") (name "/A1_IN") (class "Default")
      (node (ref "D17") (pin "3") (pinfunction "C_3") (pintype "passive"))
      (node (ref "R18") (pin "1") (pinfunction "1_1") (pintype "passive"))
      (node (ref "U17") (pin "60") (pinfunction "PF1(ADC1)_60") (pintype "bidirectional"))
    )
    (net (code "11") (name "/A2") (class "Default")
      (node (ref "JP5") (pin "3") (pinfunction "3_3") (pintype "passive"))
      (node (ref "R19") (pin "2") (pinfunction "2_2") (pintype "passive"))
    )
    (net (code "12") (name "/A2_IN") (class "Default")
      (node (ref "D18") (pin "3") (pinfunction "C_3") (pintype "passive"))
      (node (ref "R19") (pin "1") (pinfunction "1_1") (pintype "passive"))
      (node (ref "U17") (pin "59") (pinfunction "PF2(ADC2)_59") (pintype "bidirectional"))
    )
    (net (code "13") (name "/A3") (class "Default")
      (node (ref "JP5") (pin "4") (pinfunction "4_4") (pintype "passive"))
      (node (ref "R20") (pin "2") (pinfunction "2_2") (pintype "passive"))
    )
    (net (code "14") (name "/A3_IN") (class "Default")
      (node (ref "D19") (pin "3") (pinfunction "C_3") (pintype "passive"))
      (node (ref "R20") (pin "1") (pinfunction "1_1") (pintype "passive"))
      (node (ref "U17") (pin "58") (pinfunction "PF3(ADC3)_58") (pintype "bidirectional"))
    )
    (net (code "15") (name "/A4") (class "Default")
      (node (ref "JP5") (pin "5") (pinfunction "5_5") (pintype "passive"))
      (node (ref "R21") (pin "2") (pinfunction "2_2") (pintype "passive"))
    )
    (net (code "16") (name "/A4_IN") (class "Default")
      (node (ref "D20") (pin "3") (pinfunction "C_3") (pintype "passive"))
      (node (ref "R21") (pin "1") (pinfunction "1_1") (pintype "passive"))
      (node (ref "U17") (pin "57") (pinfunction "PF4(ADC4)_57") (pintype "bidirectional"))
    )
    (net (code "17") (name "/A5") (class "Default")
      (node (ref "JP5") (pin "6") (pinfunction "6_6") (pintype "passive"))
      (node (ref "R22") (pin "2") (pinfunction "2_2") (pintype "passive"))
    )
    (net (code "18") (name "/A5_IN") (class "Default")
      (node (ref "D21") (pin "3") (pinfunction "C_3") (pintype "passive"))
      (node (ref "R22") (pin "1") (pinfunction "1_1") (pintype "passive"))
      (node (ref "U17") (pin "56") (pinfunction "PF5(ADC5)_56") (pintype "bidirectional"))
    )
    (net (code "19") (name "/ACCEL_INT") (class "Default")
      (node (ref "R71") (pin "2") (pinfunction "2_2") (pintype "passive"))
      (node (ref "U17") (pin "26") (pinfunction "PD1_26") (pintype "bidirectional"))
    )
    (net (code "20") (name "/ACCEL_INT1") (class "Default")
      (node (ref "R71") (pin "1") (pinfunction "1_1") (pintype "passive"))
      (node (ref "U$8") (pin "P$11") (pinfunction "INT1_P$11") (pintype "bidirectional"))
    )
    (net (code "21") (name "/AOUT1") (class "Default")
      (node (ref "U$19") (pin "L") (pinfunction "L_L") (pintype "bidirectional"))
      (node (ref "U9") (pin "P$3") (pinfunction "OUT1_P$3") (pintype "bidirectional"))
    )
    (net (code "22") (name "/AOUT2") (class "Default")
      (node (ref "U$19") (pin "R") (pinfunction "R_R") (pintype "bidirectional"))
      (node (ref "U9") (pin "P$4") (pinfunction "OUT2_P$4") (pintype "bidirectional"))
    )
    (net (code "23") (name "/AREF") (class "Default")
      (node (ref "JP2") (pin "8") (pinfunction "8_8") (pintype "passive"))
      (node (ref "R59") (pin "2") (pinfunction "2_2") (pintype "passive"))
    )
    (net (code "24") (name "/AREF_IN") (class "Default")
      (node (ref "D32") (pin "3") (pinfunction "C_3") (pintype "passive"))
      (node (ref "R59") (pin "1") (pinfunction "1_1") (pintype "passive"))
      (node (ref "U17") (pin "62") (pinfunction "AREF_62") (pintype "bidirectional"))
    )
    (net (code "25") (name "/BOUT1") (class "Default")
      (node (ref "U$20") (pin "L") (pinfunction "L_L") (pintype "bidirectional"))
      (node (ref "U10") (pin "P$3") (pinfunction "OUT1_P$3") (pintype "bidirectional"))
    )
    (net (code "26") (name "/BOUT2") (class "Default")
      (node (ref "U$20") (pin "R") (pinfunction "R_R") (pintype "bidirectional"))
      (node (ref "U10") (pin "P$4") (pinfunction "OUT2_P$4") (pintype "bidirectional"))
    )
    (net (code "27") (name "/BT_PWR") (class "Default")
      (node (ref "Q5") (pin "1") (pinfunction "G_1") (pintype "bidirectional"))
      (node (ref "R55") (pin "1") (pinfunction "1_1") (pintype "passive"))
    )
    (net (code "28") (name "/BT_RX") (class "Default")
      (node (ref "R61") (pin "2") (pinfunction "2_2") (pintype "passive"))
      (node (ref "R69") (pin "1") (pinfunction "1_1") (pintype "passive"))
      (node (ref "U17") (pin "5") (pinfunction "PE3_5") (pintype "bidirectional"))
    )
    (net (code "29") (name "/BT_TX") (class "Default")
      (node (ref "R70") (pin "1") (pinfunction "1_1") (pintype "passive"))
      (node (ref "U$7") (pin "P$5") (pinfunction "UART_TX_P$5") (pintype "bidirectional"))
      (node (ref "U17") (pin "4") (pinfunction "PE2_4") (pintype "bidirectional"))
    )
    (net (code "30") (name "/D0") (class "Default")
      (node (ref "JP1") (pin "1") (pinfunction "1_1") (pintype "passive"))
      (node (ref "JP11") (pin "1") (pinfunction "1_1") (pintype "bidirectional"))
      (node (ref "R9") (pin "2") (pinfunction "2_2") (pintype "passive"))
    )
    (net (code "31") (name "/D0_IN") (class "Default")
      (node (ref "D9") (pin "3") (pinfunction "C_3") (pintype "passive"))
      (node (ref "R9") (pin "1") (pinfunction "1_1") (pintype "passive"))
      (node (ref "U17") (pin "2") (pinfunction "PE0(RXD)_2") (pintype "bidirectional"))
    )
    (net (code "32") (name "/D1") (class "Default")
      (node (ref "JP1") (pin "2") (pinfunction "2_2") (pintype "passive"))
      (node (ref "JP11") (pin "2") (pinfunction "2_2") (pintype "bidirectional"))
      (node (ref "R10") (pin "2") (pinfunction "2_2") (pintype "passive"))
    )
    (net (code "33") (name "/D1_IN") (class "Default")
      (node (ref "D10") (pin "3") (pinfunction "C_3") (pintype "passive"))
      (node (ref "R10") (pin "1") (pinfunction "1_1") (pintype "passive"))
      (node (ref "U17") (pin "3") (pinfunction "PE1(TXD)_3") (pintype "bidirectional"))
    )
    (net (code "34") (name "/D2") (class "Default")
      (node (ref "JP1") (pin "3") (pinfunction "3_3") (pintype "passive"))
      (node (ref "R11") (pin "2") (pinfunction "2_2") (pintype "passive"))
    )
    (net (code "35") (name "/D2_IN") (class "Default")
      (node (ref "D11") (pin "3") (pinfunction "C_3") (pintype "passive"))
      (node (ref "R11") (pin "1") (pinfunction "1_1") (pintype "passive"))
      (node (ref "U17") (pin "18") (pinfunction "PG3_18") (pintype "bidirectional"))
    )
    (net (code "36") (name "/D3") (class "Default")
      (node (ref "JP1") (pin "4") (pinfunction "4_4") (pintype "passive"))
      (node (ref "R12") (pin "2") (pinfunction "2_2") (pintype "passive"))
    )
    (net (code "37") (name "/D3_IN") (class "Default")
      (node (ref "D12") (pin "3") (pinfunction "C_3") (pintype "passive"))
      (node (ref "R12") (pin "1") (pinfunction "1_1") (pintype "passive"))
      (node (ref "U17") (pin "19") (pinfunction "PG4_19") (pintype "bidirectional"))
    )
    (net (code "38") (name "/D4") (class "Default")
      (node (ref "JP1") (pin "5") (pinfunction "5_5") (pintype "passive"))
      (node (ref "R13") (pin "2") (pinfunction "2_2") (pintype "passive"))
    )
    (net (code "39") (name "/D4_IN") (class "Default")
      (node (ref "D13") (pin "3") (pinfunction "C_3") (pintype "passive"))
      (node (ref "R13") (pin "1") (pinfunction "1_1") (pintype "passive"))
      (node (ref "U17") (pin "8") (pinfunction "PE6_8") (pintype "bidirectional"))
    )
    (net (code "40") (name "/D5") (class "Default")
      (node (ref "JP1") (pin "6") (pinfunction "6_6") (pintype "passive"))
      (node (ref "R14") (pin "2") (pinfunction "2_2") (pintype "passive"))
    )
    (net (code "41") (name "/D5_IN") (class "Default")
      (node (ref "D14") (pin "3") (pinfunction "C_3") (pintype "passive"))
      (node (ref "R14") (pin "1") (pinfunction "1_1") (pintype "passive"))
      (node (ref "U17") (pin "15") (pinfunction "PB5(OC1A)_15") (pintype "bidirectional"))
    )
    (net (code "42") (name "/D6") (class "Default")
      (node (ref "JP1") (pin "7") (pinfunction "7_7") (pintype "passive"))
      (node (ref "R15") (pin "2") (pinfunction "2_2") (pintype "passive"))
    )
    (net (code "43") (name "/D6_IN") (class "Default")
      (node (ref "D15") (pin "3") (pinfunction "C_3") (pintype "passive"))
      (node (ref "R15") (pin "1") (pinfunction "1_1") (pintype "passive"))
      (node (ref "U17") (pin "16") (pinfunction "PB6(OC1B)_16") (pintype "bidirectional"))
    )
    (net (code "44") (name "/D7") (class "Default")
      (node (ref "JP1") (pin "8") (pinfunction "8_8") (pintype "passive"))
      (node (ref "R16") (pin "2") (pinfunction "2_2") (pintype "passive"))
    )
    (net (code "45") (name "/D7_IN") (class "Default")
      (node (ref "D22") (pin "3") (pinfunction "C_3") (pintype "passive"))
      (node (ref "R16") (pin "1") (pinfunction "1_1") (pintype "passive"))
      (node (ref "U17") (pin "40") (pinfunction "PC5_40") (pintype "bidirectional"))
    )
    (net (code "46") (name "/D8") (class "Default")
      (node (ref "JP2") (pin "1") (pinfunction "1_1") (pintype "passive"))
      (node (ref "R1") (pin "2") (pinfunction "2_2") (pintype "passive"))
    )
    (net (code "47") (name "/D8_IN") (class "Default")
      (node (ref "D1") (pin "3") (pinfunction "C_3") (pintype "passive"))
      (node (ref "R1") (pin "1") (pinfunction "1_1") (pintype "passive"))
      (node (ref "U17") (pin "41") (pinfunction "PC6_41") (pintype "bidirectional"))
    )
    (net (code "48") (name "/D9") (class "Default")
      (node (ref "JP2") (pin "2") (pinfunction "2_2") (pintype "passive"))
      (node (ref "R2") (pin "2") (pinfunction "2_2") (pintype "passive"))
    )
    (net (code "49") (name "/D9_IN") (class "Default")
      (node (ref "D2") (pin "3") (pinfunction "C_3") (pintype "passive"))
      (node (ref "R2") (pin "1") (pinfunction "1_1") (pintype "passive"))
      (node (ref "U17") (pin "42") (pinfunction "PC7_42") (pintype "bidirectional"))
    )
    (net (code "50") (name "/D10") (class "Default")
      (node (ref "JP2") (pin "3") (pinfunction "3_3") (pintype "passive"))
      (node (ref "R3") (pin "2") (pinfunction "2_2") (pintype "passive"))
    )
    (net (code "51") (name "/D11") (class "Default")
      (node (ref "JP2") (pin "4") (pinfunction "4_4") (pintype "passive"))
      (node (ref "JP8") (pin "4") (pinfunction "4_4") (pintype "bidirectional"))
      (node (ref "R4") (pin "2") (pinfunction "2_2") (pintype "passive"))
    )
    (net (code "52") (name "/D12") (class "Default")
      (node (ref "JP2") (pin "5") (pinfunction "5_5") (pintype "passive"))
      (node (ref "JP8") (pin "1") (pinfunction "1_1") (pintype "bidirectional"))
      (node (ref "R5") (pin "2") (pinfunction "2_2") (pintype "passive"))
    )
    (net (code "53") (name "/D13") (class "Default")
      (node (ref "JP2") (pin "6") (pinfunction "6_6") (pintype "passive"))
      (node (ref "JP8") (pin "3") (pinfunction "3_3") (pintype "bidirectional"))
      (node (ref "R6") (pin "2") (pinfunction "2_2") (pintype "passive"))
    )
    (net (code "54") (name "/DMINUS") (class "Default")
      (node (ref "JP14") (pin "D-") (pinfunction "D-_D-") (pintype "bidirectional"))
      (node (ref "JP9") (pin "D-") (pinfunction "D-_D-") (pintype "bidirectional"))
      (node (ref "U1") (pin "16") (pinfunction "USBDM_16") (pintype "bidirectional"))
    )
    (net (code "55") (name "/DPLUS") (class "Default")
      (node (ref "JP14") (pin "D+") (pinfunction "D+_D+") (pintype "bidirectional"))
      (node (ref "JP9") (pin "D+") (pinfunction "D+_D+") (pintype "bidirectional"))
      (node (ref "U1") (pin "15") (pinfunction "USBDP_15") (pintype "bidirectional"))
    )
    (net (code "56") (name "/DRAIN1") (class "Default")
      (node (ref "U$6") (pin "D1@1") (pinfunction "D1_D1@1") (pintype "bidirectional"))
      (node (ref "U$6") (pin "D1@2") (pinfunction "D1_D1@2") (pintype "bidirectional"))
      (node (ref "U$6") (pin "D2@1") (pinfunction "D2_D2@1") (pintype "bidirectional"))
      (node (ref "U$6") (pin "D2@2") (pinfunction "D2_D2@2") (pintype "bidirectional"))
    )
    (net (code "57") (name "/DTR") (class "Default")
      (node (ref "C4") (pin "1") (pinfunction "1_1") (pintype "passive"))
      (node (ref "R63") (pin "1") (pinfunction "1_1") (pintype "passive"))
    )
    (net (code "58") (name "/E") (class "Default")
      (node (ref "U$1") (pin "6") (pinfunction "P$6_6") (pintype "bidirectional"))
      (node (ref "U17") (pin "39") (pinfunction "PC4_39") (pintype "bidirectional"))
    )
    (net (code "59") (name "/GND") (class "Default")
      (node (ref "C1") (pin "1") (pinfunction "1_1") (pintype "passive"))
      (node (ref "C10") (pin "2") (pinfunction "2_2") (pintype "passive"))
      (node (ref "C11") (pin "2") (pinfunction "2_2") (pintype "passive"))
      (node (ref "C12") (pin "2") (pinfunction "2_2") (pintype "passive"))
      (node (ref "C13") (pin "2") (pinfunction "2_2") (pintype "passive"))
      (node (ref "C14") (pin "2") (pinfunction "2_2") (pintype "passive"))
      (node (ref "C15") (pin "2") (pinfunction "2_2") (pintype "passive"))
      (node (ref "C16") (pin "2") (pinfunction "2_2") (pintype "passive"))
      (node (ref "C17") (pin "2") (pinfunction "2_2") (pintype "passive"))
      (node (ref "C19") (pin "2") (pinfunction "2_2") (pintype "passive"))
      (node (ref "C2") (pin "1") (pinfunction "1_1") (pintype "passive"))
      (node (ref "C20") (pin "2") (pinfunction "2_2") (pintype "passive"))
      (node (ref "C21") (pin "2") (pinfunction "2_2") (pintype "passive"))
      (node (ref "C3") (pin "-") (pinfunction "-_-") (pintype "passive"))
      (node (ref "C5") (pin "2") (pinfunction "2_2") (pintype "passive"))
      (node (ref "C6") (pin "2") (pinfunction "2_2") (pintype "passive"))
      (node (ref "C7") (pin "2") (pinfunction "2_2") (pintype "passive"))
      (node (ref "C8") (pin "2") (pinfunction "2_2") (pintype "passive"))
      (node (ref "C9") (pin "2") (pinfunction "2_2") (pintype "passive"))
      (node (ref "D1") (pin "1") (pinfunction "A_1") (pintype "passive"))
      (node (ref "D10") (pin "1") (pinfunction "A_1") (pintype "passive"))
      (node (ref "D11") (pin "1") (pinfunction "A_1") (pintype "passive"))
      (node (ref "D12") (pin "1") (pinfunction "A_1") (pintype "passive"))
      (node (ref "D13") (pin "1") (pinfunction "A_1") (pintype "passive"))
      (node (ref "D14") (pin "1") (pinfunction "A_1") (pintype "passive"))
      (node (ref "D15") (pin "1") (pinfunction "A_1") (pintype "passive"))
      (node (ref "D16") (pin "1") (pinfunction "A_1") (pintype "passive"))
      (node (ref "D17") (pin "1") (pinfunction "A_1") (pintype "passive"))
      (node (ref "D18") (pin "1") (pinfunction "A_1") (pintype "passive"))
      (node (ref "D19") (pin "1") (pinfunction "A_1") (pintype "passive"))
      (node (ref "D2") (pin "1") (pinfunction "A_1") (pintype "passive"))
      (node (ref "D20") (pin "1") (pinfunction "A_1") (pintype "passive"))
      (node (ref "D21") (pin "1") (pinfunction "A_1") (pintype "passive"))
      (node (ref "D22") (pin "1") (pinfunction "A_1") (pintype "passive"))
      (node (ref "D26") (pin "1") (pinfunction "A_1") (pintype "passive"))
      (node (ref "D27") (pin "1") (pinfunction "A_1") (pintype "passive"))
      (node (ref "D28") (pin "1") (pinfunction "A_1") (pintype "passive"))
      (node (ref "D29") (pin "1") (pinfunction "A_1") (pintype "passive"))
      (node (ref "D3") (pin "1") (pinfunction "A_1") (pintype "passive"))
      (node (ref "D32") (pin "1") (pinfunction "A_1") (pintype "passive"))
      (node (ref "D33") (pin "C") (pinfunction "C_C") (pintype "passive"))
      (node (ref "D4") (pin "1") (pinfunction "A_1") (pintype "passive"))
      (node (ref "D5") (pin "1") (pinfunction "A_1") (pintype "passive"))
      (node (ref "D6") (pin "1") (pinfunction "A_1") (pintype "passive"))
      (node (ref "D7") (pin "1") (pinfunction "A_1") (pintype "passive"))
      (node (ref "D8") (pin "1") (pinfunction "A_1") (pintype "passive"))
      (node (ref "D9") (pin "1") (pinfunction "A_1") (pintype "passive"))
      (node (ref "IR") (pin "3") (pinfunction "3_3") (pintype "passive"))
      (node (ref "J1") (pin "GND") (pinfunction "GND_GND") (pintype "bidirectional"))
      (node (ref "J1") (pin "GNDBREAK") (pinfunction "GNDBREAK_GNDBREAK") (pintype "bidirectional"))
      (node (ref "JP10") (pin "5") (pinfunction "5_5") (pintype "bidirectional"))
      (node (ref "JP10") (pin "6") (pinfunction "6_6") (pintype "bidirectional"))
      (node (ref "JP11") (pin "5") (pinfunction "5_5") (pintype "bidirectional"))
      (node (ref "JP11") (pin "6") (pinfunction "6_6") (pintype "bidirectional"))
      (node (ref "JP13") (pin "3") (pinfunction "3_3") (pintype "passive"))
      (node (ref "JP14") (pin "GND") (pinfunction "GND_GND") (pintype "bidirectional"))
      (node (ref "JP14") (pin "MT1") (pinfunction "GND_MT1") (pintype "bidirectional"))
      (node (ref "JP14") (pin "MT2") (pinfunction "GND_MT2") (pintype "bidirectional"))
      (node (ref "JP2") (pin "7") (pinfunction "7_7") (pintype "passive"))
      (node (ref "JP4") (pin "6") (pinfunction "6_6") (pintype "passive"))
      (node (ref "JP4") (pin "7") (pinfunction "7_7") (pintype "passive"))
      (node (ref "JP7") (pin "1") (pinfunction "1_1") (pintype "passive"))
      (node (ref "JP7") (pin "2") (pinfunction "2_2") (pintype "passive"))
      (node (ref "JP7") (pin "3") (pinfunction "3_3") (pintype "passive"))
      (node (ref "JP7") (pin "4") (pinfunction "4_4") (pintype "passive"))
      (node (ref "JP8") (pin "6") (pinfunction "6_6") (pintype "bidirectional"))
      (node (ref "JP9") (pin "GND") (pinfunction "GND_GND") (pintype "bidirectional"))
      (node (ref "POWER") (pin "P$2") (pinfunction "P$2_P$2") (pintype "bidirectional"))
      (node (ref "R26") (pin "1") (pinfunction "1_1") (pintype "passive"))
      (node (ref "R31") (pin "1") (pinfunction "1_1") (pintype "passive"))
      (node (ref "R36") (pin "1") (pinfunction "1_1") (pintype "passive"))
      (node (ref "R41") (pin "1") (pinfunction "1_1") (pintype "passive"))
      (node (ref "R46") (pin "1") (pinfunction "1_1") (pintype "passive"))
      (node (ref "R51") (pin "1") (pinfunction "1_1") (pintype "passive"))
      (node (ref "R52") (pin "1") (pinfunction "1_1") (pintype "passive"))
      (node (ref "R53") (pin "1") (pinfunction "1_1") (pintype "passive"))
      (node (ref "R62") (pin "1") (pinfunction "1_1") (pintype "passive"))
      (node (ref "R65") (pin "2") (pinfunction "2_2") (pintype "passive"))
      (node (ref "R66") (pin "1") (pinfunction "1_1") (pintype "passive"))
      (node (ref "R73") (pin "1") (pinfunction "1_1") (pintype "passive"))
      (node (ref "RESET") (pin "1") (pinfunction "1_1") (pintype "passive"))
      (node (ref "RESET") (pin "2") (pinfunction "2_2") (pintype "passive"))
      (node (ref "S2") (pin "1") (pinfunction "1_1") (pintype "passive"))
      (node (ref "S2") (pin "2") (pinfunction "2_2") (pintype "passive"))
      (node (ref "SJ1") (pin "1") (pinfunction "1_1") (pintype "passive"))
      (node (ref "U$1") (pin "1") (pinfunction "P$1_1") (pintype "bidirectional"))
      (node (ref "U$1") (pin "5") (pinfunction "P$5_5") (pintype "bidirectional"))
      (node (ref "U$11") (pin "P$10") (pinfunction "RES2_P$10") (pintype "bidirectional"))
      (node (ref "U$11") (pin "P$11") (pinfunction "RES3_P$11") (pintype "bidirectional"))
      (node (ref "U$11") (pin "P$12") (pinfunction "GND1_P$12") (pintype "bidirectional"))
      (node (ref "U$11") (pin "P$13") (pinfunction "GND2_P$13") (pintype "bidirectional"))
      (node (ref "U$11") (pin "P$4") (pinfunction "SA0_P$4") (pintype "bidirectional"))
      (node (ref "U$11") (pin "P$8") (pinfunction "DEN_P$8") (pintype "bidirectional"))
      (node (ref "U$11") (pin "P$9") (pinfunction "RES1_P$9") (pintype "bidirectional"))
      (node (ref "U$14") (pin "P$10") (pinfunction "SA1_P$10") (pintype "bidirectional"))
      (node (ref "U$14") (pin "P$12") (pinfunction "GND_P$12") (pintype "bidirectional"))
      (node (ref "U$14") (pin "P$13") (pinfunction "RES2_P$13") (pintype "bidirectional"))
      (node (ref "U$14") (pin "P$16") (pinfunction "RST_P$16") (pintype "bidirectional"))
      (node (ref "U$14") (pin "P$3") (pinfunction "RES1_P$3") (pintype "bidirectional"))
      (node (ref "U$14") (pin "P$5") (pinfunction "GND1_P$5") (pintype "bidirectional"))
      (node (ref "U$14") (pin "P$7") (pinfunction "SA0_P$7") (pintype "bidirectional"))
      (node (ref "U$2") (pin "3") (pinfunction "E_3") (pintype "passive"))
      (node (ref "U$3") (pin "GND@N1") (pinfunction "PGND_GND@N1") (pintype "bidirectional"))
      (node (ref "U$3") (pin "GND@N2") (pinfunction "PGND_GND@N2") (pintype "bidirectional"))
      (node (ref "U$3") (pin "GND@N3") (pinfunction "PGND_GND@N3") (pintype "bidirectional"))
      (node (ref "U$3") (pin "GND@N4") (pinfunction "PGND_GND@N4") (pintype "bidirectional"))
      (node (ref "U$3") (pin "GND@N5") (pinfunction "PGND_GND@N5") (pintype "bidirectional"))
      (node (ref "U$3") (pin "GND@N6") (pinfunction "PGND_GND@N6") (pintype "bidirectional"))
      (node (ref "U$3") (pin "GND@N7") (pinfunction "PGND_GND@N7") (pintype "bidirectional"))
      (node (ref "U$3") (pin "GND@N8") (pinfunction "PGND_GND@N8") (pintype "bidirectional"))
      (node (ref "U$3") (pin "P$11") (pinfunction "PGND_P$11") (pintype "bidirectional"))
      (node (ref "U$3") (pin "P$7") (pinfunction "GND_P$7") (pintype "bidirectional"))
      (node (ref "U$5") (pin "3") (pinfunction "ANODE_3") (pintype "bidirectional"))
      (node (ref "U$7") (pin "P$1") (pinfunction "GND1_P$1") (pintype "bidirectional"))
      (node (ref "U$7") (pin "P$22") (pinfunction "GND4_P$22") (pintype "bidirectional"))
      (node (ref "U$7") (pin "P$23") (pinfunction "GND5_P$23") (pintype "bidirectional"))
      (node (ref "U$7") (pin "P$24") (pinfunction "GND6_P$24") (pintype "bidirectional"))
      (node (ref "U$8") (pin "P$10") (pinfunction "GND2_P$10") (pintype "bidirectional"))
      (node (ref "U$8") (pin "P$12") (pinfunction "GND3_P$12") (pintype "bidirectional"))
      (node (ref "U$8") (pin "P$13") (pinfunction "NC3_P$13") (pintype "bidirectional"))
      (node (ref "U$8") (pin "P$5") (pinfunction "GND1_P$5") (pintype "bidirectional"))
      (node (ref "U$8") (pin "P$7") (pinfunction "SA0_P$7") (pintype "bidirectional"))
      (node (ref "U$8") (pin "P$8") (pinfunction "NC2_P$8") (pintype "bidirectional"))
      (node (ref "U1") (pin "18") (pinfunction "GND2_18") (pintype "power_in"))
      (node (ref "U1") (pin "21") (pinfunction "GND3_21") (pintype "power_in"))
      (node (ref "U1") (pin "25") (pinfunction "AGND_25") (pintype "power_in"))
      (node (ref "U1") (pin "26") (pinfunction "TEST_26") (pintype "input"))
      (node (ref "U1") (pin "7") (pinfunction "GND1_7") (pintype "power_in"))
      (node (ref "U10") (pin "GND") (pinfunction "GND_PPAD_GND") (pintype "bidirectional"))
      (node (ref "U10") (pin "P$5") (pinfunction "GND1_P$5") (pintype "bidirectional"))
      (node (ref "U10") (pin "P$6") (pinfunction "GND2_P$6") (pintype "bidirectional"))
      (node (ref "U12") (pin "4") (pinfunction "V-_4") (pintype "power_in"))
      (node (ref "U16") (pin "4") (pinfunction "V-_4") (pintype "power_in"))
      (node (ref "U16") (pin "5") (pinfunction "+IN_5") (pintype "input"))
      (node (ref "U16") (pin "6") (pinfunction "-IN_6") (pintype "input"))
      (node (ref "U17") (pin "22") (pinfunction "GND1_22") (pintype "bidirectional"))
      (node (ref "U17") (pin "53") (pinfunction "GND2_53") (pintype "bidirectional"))
      (node (ref "U17") (pin "63") (pinfunction "GND3_63") (pintype "bidirectional"))
      (node (ref "U7") (pin "P$2") (pinfunction "GND_P$2") (pintype "bidirectional"))
      (node (ref "U8") (pin "P$2") (pinfunction "GND_P$2") (pintype "bidirectional"))
      (node (ref "U9") (pin "GND") (pinfunction "GND_PPAD_GND") (pintype "bidirectional"))
      (node (ref "U9") (pin "P$5") (pinfunction "GND1_P$5") (pintype "bidirectional"))
      (node (ref "U9") (pin "P$6") (pinfunction "GND2_P$6") (pintype "bidirectional"))
    )
    (net (code "60") (name "/IR") (class "Default")
      (node (ref "IR") (pin "1") (pinfunction "1_1") (pintype "passive"))
      (node (ref "U17") (pin "25") (pinfunction "PD0_25") (pintype "bidirectional"))
    )
    (net (code "61") (name "/LCD0") (class "Default")
      (node (ref "R34") (pin "2") (pinfunction "2_2") (pintype "passive"))
      (node (ref "U17") (pin "51") (pinfunction "PA0_51") (pintype "bidirectional"))
    )
    (net (code "62") (name "/LCD1") (class "Default")
      (node (ref "U$1") (pin "8") (pinfunction "P$8_8") (pintype "bidirectional"))
      (node (ref "U17") (pin "50") (pinfunction "PA1_50") (pintype "bidirectional"))
    )
    (net (code "63") (name "/LCD2") (class "Default")
      (node (ref "U$1") (pin "9") (pinfunction "P$9_9") (pintype "bidirectional"))
      (node (ref "U17") (pin "49") (pinfunction "PA2_49") (pintype "bidirectional"))
    )
    (net (code "64") (name "/LCD3") (class "Default")
      (node (ref "U$1") (pin "10") (pinfunction "P$10_10") (pintype "bidirectional"))
      (node (ref "U17") (pin "48") (pinfunction "PA3_48") (pintype "bidirectional"))
    )
    (net (code "65") (name "/LCD4") (class "Default")
      (node (ref "U$1") (pin "11") (pinfunction "P$11_11") (pintype "bidirectional"))
      (node (ref "U17") (pin "47") (pinfunction "PA4_47") (pintype "bidirectional"))
    )
    (net (code "66") (name "/LCD5") (class "Default")
      (node (ref "U$1") (pin "12") (pinfunction "P$12_12") (pintype "bidirectional"))
      (node (ref "U17") (pin "46") (pinfunction "PA5_46") (pintype "bidirectional"))
    )
    (net (code "67") (name "/LCD6") (class "Default")
      (node (ref "U$1") (pin "13") (pinfunction "P$13_13") (pintype "bidirectional"))
      (node (ref "U17") (pin "45") (pinfunction "PA6_45") (pintype "bidirectional"))
    )
    (net (code "68") (name "/LCD7") (class "Default")
      (node (ref "U$1") (pin "14") (pinfunction "P$14_14") (pintype "bidirectional"))
      (node (ref "U17") (pin "44") (pinfunction "PA7_44") (pintype "bidirectional"))
    )
    (net (code "69") (name "/LED0") (class "Default")
      (node (ref "D30") (pin "A") (pinfunction "A_A") (pintype "passive"))
      (node (ref "U17") (pin "34") (pinfunction "PG1_34") (pintype "bidirectional"))
    )
    (net (code "70") (name "/LED1") (class "Default")
      (node (ref "D31") (pin "A") (pinfunction "A_A") (pintype "passive"))
      (node (ref "U17") (pin "33") (pinfunction "PG0_33") (pintype "bidirectional"))
    )
    (net (code "71") (name "/M0_DIR0") (class "Default")
      (node (ref "U17") (pin "29") (pinfunction "PD4_29") (pintype "bidirectional"))
      (node (ref "U9") (pin "P$9") (pinfunction "IN1_P$9") (pintype "bidirectional"))
    )
    (net (code "72") (name "/M0_DIR1") (class "Default")
      (node (ref "U17") (pin "30") (pinfunction "PD5_30") (pintype "bidirectional"))
      (node (ref "U9") (pin "P$11") (pinfunction "IN2_P$11") (pintype "bidirectional"))
    )
    (net (code "73") (name "/M0_EN") (class "Default")
      (node (ref "U17") (pin "14") (pinfunction "PB4(OC0A)_14") (pintype "bidirectional"))
      (node (ref "U9") (pin "P$10") (pinfunction "EN1_P$10") (pintype "bidirectional"))
      (node (ref "U9") (pin "P$12") (pinfunction "EN2_P$12") (pintype "bidirectional"))
    )
    (net (code "74") (name "/M1_DIR0") (class "Default")
      (node (ref "U10") (pin "P$9") (pinfunction "IN1_P$9") (pintype "bidirectional"))
      (node (ref "U17") (pin "31") (pinfunction "PD6_31") (pintype "bidirectional"))
    )
    (net (code "75") (name "/M1_DIR1") (class "Default")
      (node (ref "U10") (pin "P$11") (pinfunction "IN2_P$11") (pintype "bidirectional"))
      (node (ref "U17") (pin "32") (pinfunction "PD7_32") (pintype "bidirectional"))
    )
    (net (code "76") (name "/M1_EN") (class "Default")
      (node (ref "U10") (pin "P$10") (pinfunction "EN1_P$10") (pintype "bidirectional"))
      (node (ref "U10") (pin "P$12") (pinfunction "EN2_P$12") (pintype "bidirectional"))
      (node (ref "U17") (pin "17") (pinfunction "PB7(OC2A)_17") (pintype "bidirectional"))
    )
    (net (code "77") (name "/MISO") (class "Default")
      (node (ref "D5") (pin "3") (pinfunction "C_3") (pintype "passive"))
      (node (ref "R5") (pin "1") (pinfunction "1_1") (pintype "passive"))
      (node (ref "U17") (pin "13") (pinfunction "PB3(MISO)_13") (pintype "bidirectional"))
    )
    (net (code "78") (name "/MOSI") (class "Default")
      (node (ref "D4") (pin "3") (pinfunction "C_3") (pintype "passive"))
      (node (ref "R4") (pin "1") (pinfunction "1_1") (pintype "passive"))
      (node (ref "U17") (pin "12") (pinfunction "PB2(MOSI)_12") (pintype "bidirectional"))
    )
    (net (code "79") (name "/N$9") (class "Default")
      (node (ref "F2") (pin "1") (pinfunction "1_1") (pintype "passive"))
      (node (ref "JP14") (pin "VBUS") (pinfunction "VBUS_VBUS") (pintype "bidirectional"))
      (node (ref "JP9") (pin "VBUS") (pinfunction "VBUS_VBUS") (pintype "bidirectional"))
    )
    (net (code "80") (name "/N$33") (class "Default")
      (node (ref "Q5") (pin "3") (pinfunction "D_3") (pintype "bidirectional"))
      (node (ref "U$7") (pin "P$21") (pinfunction "VDD_P$21") (pintype "bidirectional"))
    )
    (net (code "81") (name "/PWR_GATE1") (class "Default")
      (node (ref "D37") (pin "A") (pinfunction "A_A") (pintype "passive"))
      (node (ref "R72") (pin "2") (pinfunction "2_2") (pintype "passive"))
      (node (ref "U$6") (pin "G1") (pinfunction "G1_G1") (pintype "bidirectional"))
    )
    (net (code "82") (name "/PWR_GATE2") (class "Default")
      (node (ref "D36") (pin "A") (pinfunction "A_A") (pintype "passive"))
      (node (ref "R42") (pin "1") (pinfunction "1_1") (pintype "passive"))
      (node (ref "U$6") (pin "G2") (pinfunction "G2_G2") (pintype "bidirectional"))
    )
    (net (code "83") (name "/PWR_SW") (class "Default")
      (node (ref "D35") (pin "C") (pinfunction "C_C") (pintype "passive"))
      (node (ref "D36") (pin "C") (pinfunction "C_C") (pintype "passive"))
      (node (ref "D38") (pin "C") (pinfunction "C_C") (pintype "passive"))
      (node (ref "Q2") (pin "2") (pinfunction "S_2") (pintype "bidirectional"))
      (node (ref "R44") (pin "1") (pinfunction "1_1") (pintype "passive"))
      (node (ref "R67") (pin "2") (pinfunction "2_2") (pintype "passive"))
      (node (ref "U$6") (pin "S2") (pinfunction "S2_S2") (pintype "bidirectional"))
    )
    (net (code "84") (name "/RESET") (class "Default")
      (node (ref "R39") (pin "2") (pinfunction "2_2") (pintype "passive"))
      (node (ref "R40") (pin "2") (pinfunction "2_2") (pintype "passive"))
      (node (ref "R54") (pin "1") (pinfunction "1_1") (pintype "passive"))
      (node (ref "R56") (pin "1") (pinfunction "1_1") (pintype "passive"))
      (node (ref "RESET") (pin "3") (pinfunction "3_3") (pintype "passive"))
      (node (ref "RESET") (pin "4") (pinfunction "4_4") (pintype "passive"))
      (node (ref "U17") (pin "20") (pinfunction "RESET/PG5_20") (pintype "bidirectional"))
    )
    (net (code "85") (name "/RS") (class "Default")
      (node (ref "R33") (pin "1") (pinfunction "1_1") (pintype "passive"))
      (node (ref "U17") (pin "54") (pinfunction "PF7(ADC7)_54") (pintype "bidirectional"))
    )
    (net (code "86") (name "/RX") (class "Default")
      (node (ref "U1") (pin "1") (pinfunction "TXD_1") (pintype "output"))
      (node (ref "U17") (pin "28") (pinfunction "PD3_28") (pintype "bidirectional"))
    )
    (net (code "87") (name "/SCK") (class "Default")
      (node (ref "D6") (pin "3") (pinfunction "C_3") (pintype "passive"))
      (node (ref "R6") (pin "1") (pinfunction "1_1") (pintype "passive"))
      (node (ref "U17") (pin "11") (pinfunction "PB1(SCK)_11") (pintype "bidirectional"))
    )
    (net (code "88") (name "/SCL0") (class "Default")
      (node (ref "JP2") (pin "9") (pinfunction "9_9") (pintype "passive"))
      (node (ref "R7") (pin "2") (pinfunction "2_2") (pintype "passive"))
    )
    (net (code "89") (name "/SCL_5V") (class "Default")
      (node (ref "R60") (pin "1") (pinfunction "1_1") (pintype "passive"))
      (node (ref "U$10") (pin "3") (pinfunction "D_3") (pintype "bidirectional"))
      (node (ref "U17") (pin "6") (pinfunction "PE4(SCL)_6") (pintype "bidirectional"))
    )
    (net (code "90") (name "/SCL_IN") (class "Default")
      (node (ref "D7") (pin "3") (pinfunction "C_3") (pintype "passive"))
      (node (ref "R38") (pin "1") (pinfunction "1_1") (pintype "passive"))
      (node (ref "R7") (pin "1") (pinfunction "1_1") (pintype "passive"))
      (node (ref "U$10") (pin "2") (pinfunction "S_2") (pintype "bidirectional"))
      (node (ref "U$11") (pin "P$2") (pinfunction "SCL_P$2") (pintype "bidirectional"))
      (node (ref "U$14") (pin "P$4") (pinfunction "SCL_P$4") (pintype "bidirectional"))
      (node (ref "U$8") (pin "P$4") (pinfunction "SCL_P$4") (pintype "bidirectional"))
    )
    (net (code "91") (name "/SDA0") (class "Default")
      (node (ref "JP2") (pin "10") (pinfunction "10_10") (pintype "passive"))
      (node (ref "R8") (pin "2") (pinfunction "2_2") (pintype "passive"))
    )
    (net (code "92") (name "/SDA_5V") (class "Default")
      (node (ref "R58") (pin "1") (pinfunction "1_1") (pintype "passive"))
      (node (ref "U$9") (pin "3") (pinfunction "D_3") (pintype "bidirectional"))
      (node (ref "U17") (pin "7") (pinfunction "PE5(SDA)_7") (pintype "bidirectional"))
    )
    (net (code "93") (name "/SDA_IN") (class "Default")
      (node (ref "D8") (pin "3") (pinfunction "C_3") (pintype "passive"))
      (node (ref "R37") (pin "1") (pinfunction "1_1") (pintype "passive"))
      (node (ref "R8") (pin "1") (pinfunction "1_1") (pintype "passive"))
      (node (ref "U$11") (pin "P$3") (pinfunction "SDA_P$3") (pintype "bidirectional"))
      (node (ref "U$14") (pin "P$6") (pinfunction "SDA_P$6") (pintype "bidirectional"))
      (node (ref "U$8") (pin "P$6") (pinfunction "SDA_P$6") (pintype "bidirectional"))
      (node (ref "U$9") (pin "2") (pinfunction "S_2") (pintype "bidirectional"))
    )
    (net (code "94") (name "/SERVO0") (class "Default")
      (node (ref "JP3") (pin "1") (pinfunction "1_1") (pintype "passive"))
      (node (ref "R47") (pin "2") (pinfunction "2_2") (pintype "passive"))
    )
    (net (code "95") (name "/SERVO0_IN") (class "Default")
      (node (ref "D26") (pin "3") (pinfunction "C_3") (pintype "passive"))
      (node (ref "R47") (pin "1") (pinfunction "1_1") (pintype "passive"))
      (node (ref "U17") (pin "35") (pinfunction "PC0_35") (pintype "bidirectional"))
    )
    (net (code "96") (name "/SERVO1") (class "Default")
      (node (ref "JP3") (pin "2") (pinfunction "2_2") (pintype "passive"))
      (node (ref "R48") (pin "2") (pinfunction "2_2") (pintype "passive"))
    )
    (net (code "97") (name "/SERVO1_IN") (class "Default")
      (node (ref "D27") (pin "3") (pinfunction "C_3") (pintype "passive"))
      (node (ref "R48") (pin "1") (pinfunction "1_1") (pintype "passive"))
      (node (ref "U17") (pin "36") (pinfunction "PC1_36") (pintype "bidirectional"))
    )
    (net (code "98") (name "/SERVO2") (class "Default")
      (node (ref "JP3") (pin "3") (pinfunction "3_3") (pintype "passive"))
      (node (ref "R49") (pin "2") (pinfunction "2_2") (pintype "passive"))
    )
    (net (code "99") (name "/SERVO2_IN") (class "Default")
      (node (ref "D28") (pin "3") (pinfunction "C_3") (pintype "passive"))
      (node (ref "R49") (pin "1") (pinfunction "1_1") (pintype "passive"))
      (node (ref "U17") (pin "37") (pinfunction "PC2_37") (pintype "bidirectional"))
    )
    (net (code "100") (name "/SERVO3") (class "Default")
      (node (ref "JP3") (pin "4") (pinfunction "4_4") (pintype "passive"))
      (node (ref "R50") (pin "2") (pinfunction "2_2") (pintype "passive"))
    )
    (net (code "101") (name "/SERVO3_IN") (class "Default")
      (node (ref "D29") (pin "3") (pinfunction "C_3") (pintype "passive"))
      (node (ref "R50") (pin "1") (pinfunction "1_1") (pintype "passive"))
      (node (ref "U17") (pin "38") (pinfunction "PC3_38") (pintype "bidirectional"))
    )
    (net (code "102") (name "/SS") (class "Default")
      (node (ref "D3") (pin "3") (pinfunction "C_3") (pintype "passive"))
      (node (ref "R3") (pin "1") (pinfunction "1_1") (pintype "passive"))
      (node (ref "U17") (pin "10") (pinfunction "PB0(SS)_10") (pintype "bidirectional"))
    )
    (net (code "103") (name "/SW1") (class "Default")
      (node (ref "S2") (pin "3") (pinfunction "3_3") (pintype "passive"))
      (node (ref "S2") (pin "4") (pinfunction "4_4") (pintype "passive"))
      (node (ref "U17") (pin "9") (pinfunction "PE7_9") (pintype "bidirectional"))
    )
    (net (code "104") (name "/TX") (class "Default")
      (node (ref "U1") (pin "5") (pinfunction "RXD_5") (pintype "input"))
      (node (ref "U17") (pin "27") (pinfunction "PD2_27") (pintype "bidirectional"))
    )
    (net (code "105") (name "/USB_2.5V") (class "Default")
      (node (ref "R64") (pin "1") (pinfunction "1_1") (pintype "passive"))
      (node (ref "R66") (pin "2") (pinfunction "2_2") (pintype "passive"))
      (node (ref "SJ1") (pin "2") (pinfunction "2_2") (pintype "passive"))
      (node (ref "U16") (pin "3") (pinfunction "+IN_3") (pintype "input"))
    )
    (net (code "106") (name "/USB_5V") (class "Default")
      (node (ref "D35") (pin "A") (pinfunction "A_A") (pintype "passive"))
      (node (ref "F2") (pin "2") (pinfunction "2_2") (pintype "passive"))
      (node (ref "R64") (pin "2") (pinfunction "2_2") (pintype "passive"))
    )
    (net (code "107") (name "/VIN") (class "Default")
      (node (ref "J1") (pin "PWR") (pinfunction "PWR_PWR") (pintype "bidirectional"))
      (node (ref "R35") (pin "2") (pinfunction "2_2") (pintype "passive"))
      (node (ref "U$12") (pin "1") (pinfunction "1_1") (pintype "passive"))
    )
    (net (code "108") (name "/VIN1") (class "Default")
      (node (ref "D37") (pin "C") (pinfunction "C_C") (pintype "passive"))
      (node (ref "D39") (pin "A") (pinfunction "A_A") (pintype "passive"))
      (node (ref "R32") (pin "2") (pinfunction "2_2") (pintype "passive"))
      (node (ref "U$12") (pin "2") (pinfunction "2_2") (pintype "passive"))
      (node (ref "U$6") (pin "S1") (pinfunction "S1_S1") (pintype "bidirectional"))
    )
    (net (code "109") (name "/VIN_F") (class "Default")
      (node (ref "C13") (pin "1") (pinfunction "1_1") (pintype "passive"))
      (node (ref "C18") (pin "2") (pinfunction "2_2") (pintype "passive"))
      (node (ref "JP6") (pin "1") (pinfunction "1_1") (pintype "passive"))
      (node (ref "JP6") (pin "2") (pinfunction "2_2") (pintype "passive"))
      (node (ref "JP6") (pin "3") (pinfunction "3_3") (pintype "passive"))
      (node (ref "JP6") (pin "4") (pinfunction "4_4") (pintype "passive"))
      (node (ref "Q2") (pin "3") (pinfunction "D_3") (pintype "bidirectional"))
      (node (ref "R45") (pin "2") (pinfunction "2_2") (pintype "passive"))
      (node (ref "U$13") (pin "1") (pinfunction "1_1") (pintype "passive"))
      (node (ref "U$3") (pin "P$2") (pinfunction "VIN_P$2") (pintype "bidirectional"))
      (node (ref "U$3") (pin "P$3") (pinfunction "EN_P$3") (pintype "bidirectional"))
      (node (ref "U$3") (pin "P$4") (pinfunction "PS/SYNC_P$4") (pintype "bidirectional"))
      (node (ref "U10") (pin "P$1") (pinfunction "VM1_P$1") (pintype "bidirectional"))
      (node (ref "U10") (pin "P$2") (pinfunction "VM2_P$2") (pintype "bidirectional"))
      (node (ref "U9") (pin "P$1") (pinfunction "VM1_P$1") (pintype "bidirectional"))
      (node (ref "U9") (pin "P$2") (pinfunction "VM2_P$2") (pintype "bidirectional"))
    )
    (net (code "110") (name "/VREG_OUT") (class "Default")
      (node (ref "C11") (pin "1") (pinfunction "1_1") (pintype "passive"))
      (node (ref "C12") (pin "1") (pinfunction "1_1") (pintype "passive"))
      (node (ref "F3") (pin "1") (pinfunction "1_1") (pintype "passive"))
      (node (ref "U$3") (pin "P$8") (pinfunction "FB_P$8") (pintype "bidirectional"))
      (node (ref "U$3") (pin "P$9") (pinfunction "VOUT_P$9") (pintype "bidirectional"))
    )
    (net (code "111") (name "Net-(C4-Pad2)") (class "Default")
      (node (ref "C4") (pin "2") (pinfunction "2_2") (pintype "passive"))
      (node (ref "R39") (pin "1") (pinfunction "1_1") (pintype "passive"))
    )
    (net (code "112") (name "Net-(D23-PadA)") (class "Default")
      (node (ref "D23") (pin "A") (pinfunction "A_A") (pintype "passive"))
      (node (ref "R29") (pin "2") (pinfunction "2_2") (pintype "passive"))
    )
    (net (code "113") (name "Net-(D24-A1)") (class "Default")
      (node (ref "D24") (pin "1") (pinfunction "A1_1") (pintype "passive"))
      (node (ref "R42") (pin "2") (pinfunction "2_2") (pintype "passive"))
      (node (ref "R67") (pin "1") (pinfunction "1_1") (pintype "passive"))
    )
    (net (code "114") (name "Net-(D24-A2)") (class "Default")
      (node (ref "D24") (pin "2") (pinfunction "A2_2") (pintype "passive"))
      (node (ref "R32") (pin "1") (pinfunction "1_1") (pintype "passive"))
      (node (ref "R72") (pin "1") (pinfunction "1_1") (pintype "passive"))
    )
    (net (code "115") (name "Net-(D24-CC)") (class "Default")
      (node (ref "D24") (pin "3") (pinfunction "CC_3") (pintype "passive"))
      (node (ref "U16") (pin "1") (pinfunction "OUT_1") (pintype "output"))
    )
    (net (code "116") (name "Net-(D25-PadC)") (class "Default")
      (node (ref "D25") (pin "C") (pinfunction "C_C") (pintype "passive"))
      (node (ref "R41") (pin "2") (pinfunction "2_2") (pintype "passive"))
    )
    (net (code "117") (name "Net-(D30-PadC)") (class "Default")
      (node (ref "D30") (pin "C") (pinfunction "C_C") (pintype "passive"))
      (node (ref "R51") (pin "2") (pinfunction "2_2") (pintype "passive"))
    )
    (net (code "118") (name "Net-(D31-PadC)") (class "Default")
      (node (ref "D31") (pin "C") (pinfunction "C_C") (pintype "passive"))
      (node (ref "R52") (pin "2") (pinfunction "2_2") (pintype "passive"))
    )
    (net (code "119") (name "Net-(D33-PadA)") (class "Default")
      (node (ref "D33") (pin "A") (pinfunction "A_A") (pintype "passive"))
      (node (ref "R68") (pin "1") (pinfunction "1_1") (pintype "passive"))
    )
    (net (code "120") (name "Net-(D34-PadA)") (class "Default")
      (node (ref "D34") (pin "A") (pinfunction "A_A") (pintype "passive"))
      (node (ref "R57") (pin "2") (pinfunction "2_2") (pintype "passive"))
    )
    (net (code "121") (name "Net-(JP4-Pad3)") (class "Default")
      (node (ref "JP4") (pin "3") (pinfunction "3_3") (pintype "passive"))
      (node (ref "R56") (pin "2") (pinfunction "2_2") (pintype "passive"))
    )
    (net (code "122") (name "Net-(JP4-Pad8)") (class "Default")
      (node (ref "JP4") (pin "8") (pinfunction "8_8") (pintype "passive"))
      (node (ref "U$13") (pin "2") (pinfunction "2_2") (pintype "passive"))
    )
    (net (code "123") (name "Net-(JP8-Pad5)") (class "Default")
      (node (ref "JP8") (pin "5") (pinfunction "5_5") (pintype "bidirectional"))
      (node (ref "R54") (pin "2") (pinfunction "2_2") (pintype "passive"))
    )
    (net (code "124") (name "Net-(JP13-Pad4)") (class "Default")
      (node (ref "JP13") (pin "4") (pinfunction "4_4") (pintype "passive"))
      (node (ref "R70") (pin "2") (pinfunction "2_2") (pintype "passive"))
    )
    (net (code "125") (name "Net-(JP13-Pad5)") (class "Default")
      (node (ref "JP13") (pin "5") (pinfunction "5_5") (pintype "passive"))
      (node (ref "R69") (pin "2") (pinfunction "2_2") (pintype "passive"))
    )
    (net (code "126") (name "Net-(POWER-PadP$1)") (class "Default")
      (node (ref "POWER") (pin "P$1") (pinfunction "P$1_P$1") (pintype "bidirectional"))
      (node (ref "R43") (pin "2") (pinfunction "2_2") (pintype "passive"))
    )
    (net (code "127") (name "Net-(Q2-G)") (class "Default")
      (node (ref "C18") (pin "1") (pinfunction "1_1") (pintype "passive"))
      (node (ref "D38") (pin "A") (pinfunction "A_A") (pintype "passive"))
      (node (ref "Q2") (pin "1") (pinfunction "G_1") (pintype "bidirectional"))
      (node (ref "R43") (pin "1") (pinfunction "1_1") (pintype "passive"))
      (node (ref "R44") (pin "2") (pinfunction "2_2") (pintype "passive"))
    )
    (net (code "128") (name "Net-(Q3-G)") (class "Default")
      (node (ref "Q3") (pin "1") (pinfunction "G_1") (pintype "bidirectional"))
      (node (ref "R25") (pin "1") (pinfunction "1_1") (pintype "passive"))
      (node (ref "U12") (pin "7") (pinfunction "OUT_7") (pintype "output"))
    )
    (net (code "129") (name "Net-(Q4-G)") (class "Default")
      (node (ref "Q4") (pin "1") (pinfunction "G_1") (pintype "bidirectional"))
      (node (ref "R30") (pin "1") (pinfunction "1_1") (pintype "passive"))
      (node (ref "U12") (pin "1") (pinfunction "OUT_1") (pintype "output"))
    )
    (net (code "130") (name "Net-(U$1-P$3)") (class "Default")
      (node (ref "U$1") (pin "3") (pinfunction "P$3_3") (pintype "bidirectional"))
      (node (ref "U$2") (pin "2") (pinfunction "S_2") (pintype "passive"))
    )
    (net (code "131") (name "Net-(U$1-P$4)") (class "Default")
      (node (ref "R33") (pin "2") (pinfunction "2_2") (pintype "passive"))
      (node (ref "U$1") (pin "4") (pinfunction "P$4_4") (pintype "bidirectional"))
    )
    (net (code "132") (name "Net-(U$1-P$7)") (class "Default")
      (node (ref "R34") (pin "1") (pinfunction "1_1") (pintype "passive"))
      (node (ref "U$1") (pin "7") (pinfunction "P$7_7") (pintype "bidirectional"))
    )
    (net (code "133") (name "Net-(U$3-L1)") (class "Default")
      (node (ref "U$3") (pin "P$1") (pinfunction "L1_P$1") (pintype "bidirectional"))
      (node (ref "U$4") (pin "P$1") (pinfunction "1_P$1") (pintype "passive"))
    )
    (net (code "134") (name "Net-(U$3-L2)") (class "Default")
      (node (ref "U$3") (pin "P$10") (pinfunction "L2_P$10") (pintype "bidirectional"))
      (node (ref "U$4") (pin "P$2") (pinfunction "2_P$2") (pintype "passive"))
    )
    (net (code "135") (name "Net-(U$3-PG)") (class "Default")
      (node (ref "R28") (pin "2") (pinfunction "2_2") (pintype "passive"))
      (node (ref "U$3") (pin "P$5") (pinfunction "PG_P$5") (pintype "bidirectional"))
    )
    (net (code "136") (name "Net-(U$3-VAUX)") (class "Default")
      (node (ref "C10") (pin "1") (pinfunction "1_1") (pintype "passive"))
      (node (ref "U$3") (pin "P$6") (pinfunction "VAUX_P$6") (pintype "bidirectional"))
    )
    (net (code "137") (name "Net-(U$7-CMD)") (class "Default")
      (node (ref "R73") (pin "2") (pinfunction "2_2") (pintype "passive"))
      (node (ref "U$7") (pin "P$8") (pinfunction "CMD_P$8") (pintype "bidirectional"))
    )
    (net (code "138") (name "Net-(U$7-PIO1)") (class "Default")
      (node (ref "R68") (pin "2") (pinfunction "2_2") (pintype "passive"))
      (node (ref "U$7") (pin "P$9") (pinfunction "PIO1_P$9") (pintype "bidirectional"))
    )
    (net (code "139") (name "Net-(U$7-UART_RX)") (class "Default")
      (node (ref "R61") (pin "1") (pinfunction "1_1") (pintype "passive"))
      (node (ref "R62") (pin "2") (pinfunction "2_2") (pintype "passive"))
      (node (ref "U$7") (pin "P$6") (pinfunction "UART_RX_P$6") (pintype "bidirectional"))
    )
    (net (code "140") (name "Net-(U$8-BYP)") (class "Default")
      (node (ref "C5") (pin "1") (pinfunction "1_1") (pintype "passive"))
      (node (ref "U$8") (pin "P$2") (pinfunction "BYP_P$2") (pintype "bidirectional"))
    )
    (net (code "141") (name "Net-(U$11-CAP)") (class "Default")
      (node (ref "C16") (pin "1") (pinfunction "1_1") (pintype "passive"))
      (node (ref "U$11") (pin "P$14") (pinfunction "CAP_P$14") (pintype "bidirectional"))
    )
    (net (code "142") (name "Net-(U$14-BYP)") (class "Default")
      (node (ref "C19") (pin "1") (pinfunction "1_1") (pintype "passive"))
      (node (ref "U$14") (pin "P$2") (pinfunction "BYP_P$2") (pintype "bidirectional"))
    )
    (net (code "143") (name "Net-(U$14-CRST)") (class "Default")
      (node (ref "C20") (pin "1") (pinfunction "1_1") (pintype "passive"))
      (node (ref "U$14") (pin "P$8") (pinfunction "CRST_P$8") (pintype "bidirectional"))
    )
    (net (code "144") (name "Net-(U1-DTR)") (class "Default")
      (node (ref "R63") (pin "2") (pinfunction "2_2") (pintype "passive"))
      (node (ref "U1") (pin "2") (pinfunction "DTR_2") (pintype "bidirectional"))
    )
    (net (code "145") (name "Net-(U1-RXLED)") (class "Default")
      (node (ref "D34") (pin "C") (pinfunction "C_C") (pintype "passive"))
      (node (ref "U1") (pin "22") (pinfunction "RXLED_22") (pintype "bidirectional"))
    )
    (net (code "146") (name "Net-(U1-TXLED)") (class "Default")
      (node (ref "D23") (pin "C") (pinfunction "C_C") (pintype "passive"))
      (node (ref "U1") (pin "23") (pinfunction "TXLED_23") (pintype "bidirectional"))
    )
    (net (code "147") (name "Net-(U8-EN)") (class "Default")
      (node (ref "R65") (pin "1") (pinfunction "1_1") (pintype "passive"))
      (node (ref "U8") (pin "P$3") (pinfunction "EN_P$3") (pintype "bidirectional"))
    )
    (net (code "148") (name "Net-(U8-ILIM)") (class "Default")
      (node (ref "R53") (pin "2") (pinfunction "2_2") (pintype "passive"))
      (node (ref "U8") (pin "P$5") (pinfunction "ILIM_P$5") (pintype "bidirectional"))
    )
    (net (code "149") (name "Net-(U12A-+IN)") (class "Default")
      (node (ref "R27") (pin "1") (pinfunction "1_1") (pintype "passive"))
      (node (ref "R31") (pin "2") (pinfunction "2_2") (pintype "passive"))
      (node (ref "U12") (pin "3") (pinfunction "+IN_3") (pintype "input"))
    )
    (net (code "150") (name "Net-(U12B-+IN)") (class "Default")
      (node (ref "R24") (pin "1") (pinfunction "1_1") (pintype "passive"))
      (node (ref "R26") (pin "2") (pinfunction "2_2") (pintype "passive"))
      (node (ref "U12") (pin "5") (pinfunction "+IN_5") (pintype "input"))
    )
    (net (code "151") (name "Net-(U16A--IN)") (class "Default")
      (node (ref "R35") (pin "1") (pinfunction "1_1") (pintype "passive"))
      (node (ref "R36") (pin "2") (pinfunction "2_2") (pintype "passive"))
      (node (ref "U16") (pin "2") (pinfunction "-IN_2") (pintype "input"))
    )
    (net (code "152") (name "Net-(U16A-V+)") (class "Default")
      (node (ref "D39") (pin "C") (pinfunction "C_C") (pintype "passive"))
      (node (ref "U16") (pin "8") (pinfunction "V+_8") (pintype "power_in"))
    )
    (net (code "153") (name "Net-(U17-PF6(ADC6))") (class "Default")
      (node (ref "R45") (pin "1") (pinfunction "1_1") (pintype "passive"))
      (node (ref "R46") (pin "2") (pinfunction "2_2") (pintype "passive"))
      (node (ref "U17") (pin "55") (pinfunction "PF6(ADC6)_55") (pintype "bidirectional"))
    )
    (net (code "154") (name "Net-(U17-PG2)") (class "Default")
      (node (ref "R55") (pin "2") (pinfunction "2_2") (pintype "passive"))
      (node (ref "U17") (pin "43") (pinfunction "PG2_43") (pintype "bidirectional"))
    )
    (net (code "155") (name "Net-(U17-XTAL1)") (class "Default")
      (node (ref "C1") (pin "2") (pinfunction "2_2") (pintype "passive"))
      (node (ref "U17") (pin "24") (pinfunction "XTAL1_24") (pintype "bidirectional"))
      (node (ref "Y1") (pin "P$1") (pinfunction "1_P$1") (pintype "passive"))
    )
    (net (code "156") (name "Net-(U17-XTAL2)") (class "Default")
      (node (ref "C2") (pin "2") (pinfunction "2_2") (pintype "passive"))
      (node (ref "U17") (pin "23") (pinfunction "XTAL2_23") (pintype "bidirectional"))
      (node (ref "Y1") (pin "P$2") (pinfunction "2_P$2") (pintype "passive"))
    )
    (net (code "157") (name "unconnected-(JP4-Pad1)") (class "Default")
      (node (ref "JP4") (pin "1") (pinfunction "1_1") (pintype "passive"))
    )
    (net (code "158") (name "unconnected-(JP12-Pad1)") (class "Default")
      (node (ref "JP12") (pin "1") (pinfunction "1_1") (pintype "passive"))
    )
    (net (code "159") (name "unconnected-(JP12-Pad2)") (class "Default")
      (node (ref "JP12") (pin "2") (pinfunction "2_2") (pintype "passive"))
    )
    (net (code "160") (name "unconnected-(JP13-Pad1)") (class "Default")
      (node (ref "JP13") (pin "1") (pinfunction "1_1") (pintype "passive"))
    )
    (net (code "161") (name "unconnected-(JP13-Pad6)") (class "Default")
      (node (ref "JP13") (pin "6") (pinfunction "6_6") (pintype "passive"))
    )
    (net (code "162") (name "unconnected-(U$7-AIO0-PadP$4)") (class "Default")
      (node (ref "U$7") (pin "P$4") (pinfunction "AIO0_P$4") (pintype "bidirectional"))
    )
    (net (code "163") (name "unconnected-(U$7-AIO1-PadP$3)") (class "Default")
      (node (ref "U$7") (pin "P$3") (pinfunction "AIO1_P$3") (pintype "bidirectional"))
    )
    (net (code "164") (name "unconnected-(U$7-AIO2-PadP$2)") (class "Default")
      (node (ref "U$7") (pin "P$2") (pinfunction "AIO2_P$2") (pintype "bidirectional"))
    )
    (net (code "165") (name "unconnected-(U$7-PIO2-PadP$10)") (class "Default")
      (node (ref "U$7") (pin "P$10") (pinfunction "PIO2_P$10") (pintype "bidirectional"))
    )
    (net (code "166") (name "unconnected-(U$7-PIO3-PadP$11)") (class "Default")
      (node (ref "U$7") (pin "P$11") (pinfunction "PIO3_P$11") (pintype "bidirectional"))
    )
    (net (code "167") (name "unconnected-(U$7-PIO4-PadP$12)") (class "Default")
      (node (ref "U$7") (pin "P$12") (pinfunction "PIO4_P$12") (pintype "bidirectional"))
    )
    (net (code "168") (name "unconnected-(U$7-PIO5-PadP$13)") (class "Default")
      (node (ref "U$7") (pin "P$13") (pinfunction "PIO5_P$13") (pintype "bidirectional"))
    )
    (net (code "169") (name "unconnected-(U$7-PIO7-PadP$17)") (class "Default")
      (node (ref "U$7") (pin "P$17") (pinfunction "PIO7_P$17") (pintype "bidirectional"))
    )
    (net (code "170") (name "unconnected-(U$7-RSVD1-PadP$18)") (class "Default")
      (node (ref "U$7") (pin "P$18") (pinfunction "RSVD1_P$18") (pintype "bidirectional"))
    )
    (net (code "171") (name "unconnected-(U$7-RSVD2-PadP$19)") (class "Default")
      (node (ref "U$7") (pin "P$19") (pinfunction "RSVD2_P$19") (pintype "bidirectional"))
    )
    (net (code "172") (name "unconnected-(U$7-RSVD3-PadP$20)") (class "Default")
      (node (ref "U$7") (pin "P$20") (pinfunction "RSVD3_P$20") (pintype "bidirectional"))
    )
    (net (code "173") (name "unconnected-(U$7-RTS-PadP$16)") (class "Default")
      (node (ref "U$7") (pin "P$16") (pinfunction "RTS_P$16") (pintype "bidirectional"))
    )
    (net (code "174") (name "unconnected-(U$7-SPI-PadP$15)") (class "Default")
      (node (ref "U$7") (pin "P$15") (pinfunction "SPI_P$15") (pintype "bidirectional"))
    )
    (net (code "175") (name "unconnected-(U$7-WAKE_HW-PadP$14)") (class "Default")
      (node (ref "U$7") (pin "P$14") (pinfunction "WAKE_HW_P$14") (pintype "bidirectional"))
    )
    (net (code "176") (name "unconnected-(U$7-WAKE_SW-PadP$7)") (class "Default")
      (node (ref "U$7") (pin "P$7") (pinfunction "WAKE_SW_P$7") (pintype "bidirectional"))
    )
    (net (code "177") (name "unconnected-(U$8-INT2-PadP$9)") (class "Default")
      (node (ref "U$8") (pin "P$9") (pinfunction "INT2_P$9") (pintype "bidirectional"))
    )
    (net (code "178") (name "unconnected-(U$8-NC1-PadP$3)") (class "Default")
      (node (ref "U$8") (pin "P$3") (pinfunction "NC1_P$3") (pintype "bidirectional"))
    )
    (net (code "179") (name "unconnected-(U$11-DRDY-PadP$6)") (class "Default")
      (node (ref "U$11") (pin "P$6") (pinfunction "DRDY_P$6") (pintype "bidirectional"))
    )
    (net (code "180") (name "unconnected-(U$11-INT1-PadP$7)") (class "Default")
      (node (ref "U$11") (pin "P$7") (pinfunction "INT1_P$7") (pintype "bidirectional"))
    )
    (net (code "181") (name "unconnected-(U$14-INT1-PadP$11)") (class "Default")
      (node (ref "U$14") (pin "P$11") (pinfunction "INT1_P$11") (pintype "bidirectional"))
    )
    (net (code "182") (name "unconnected-(U$14-INT2-PadP$9)") (class "Default")
      (node (ref "U$14") (pin "P$9") (pinfunction "INT2_P$9") (pintype "bidirectional"))
    )
    (net (code "183") (name "unconnected-(U$14-NC-PadP$15)") (class "Default")
      (node (ref "U$14") (pin "P$15") (pinfunction "NC_P$15") (pintype "bidirectional"))
    )
    (net (code "184") (name "unconnected-(U1-3V3OUT-Pad17)") (class "Default")
      (node (ref "U1") (pin "17") (pinfunction "3V3OUT_17") (pintype "output"))
    )
    (net (code "185") (name "unconnected-(U1-CTS-Pad11)") (class "Default")
      (node (ref "U1") (pin "11") (pinfunction "CTS_11") (pintype "bidirectional"))
    )
    (net (code "186") (name "unconnected-(U1-RTS-Pad3)") (class "Default")
      (node (ref "U1") (pin "3") (pinfunction "RTS_3") (pintype "bidirectional"))
    )
    (net (code "187") (name "unconnected-(U7-NC-PadP$5)") (class "Default")
      (node (ref "U7") (pin "P$5") (pinfunction "NC_P$5") (pintype "bidirectional"))
    )
    (net (code "188") (name "unconnected-(U8-FAULT-PadP$4)") (class "Default")
      (node (ref "U8") (pin "P$4") (pinfunction "FAULT_P$4") (pintype "bidirectional"))
    )
    (net (code "189") (name "unconnected-(U16B-OUT-Pad7)") (class "Default")
      (node (ref "U16") (pin "7") (pinfunction "OUT_7") (pintype "output"))
    )
    (net (code "190") (name "unconnected-(U17-NC-Pad1)") (class "Default")
      (node (ref "U17") (pin "1") (pinfunction "NC_1") (pintype "bidirectional"))
    )
  )
)
